# Mainboard.net
KiCad netlist of a schematic drawn in EasyEDA
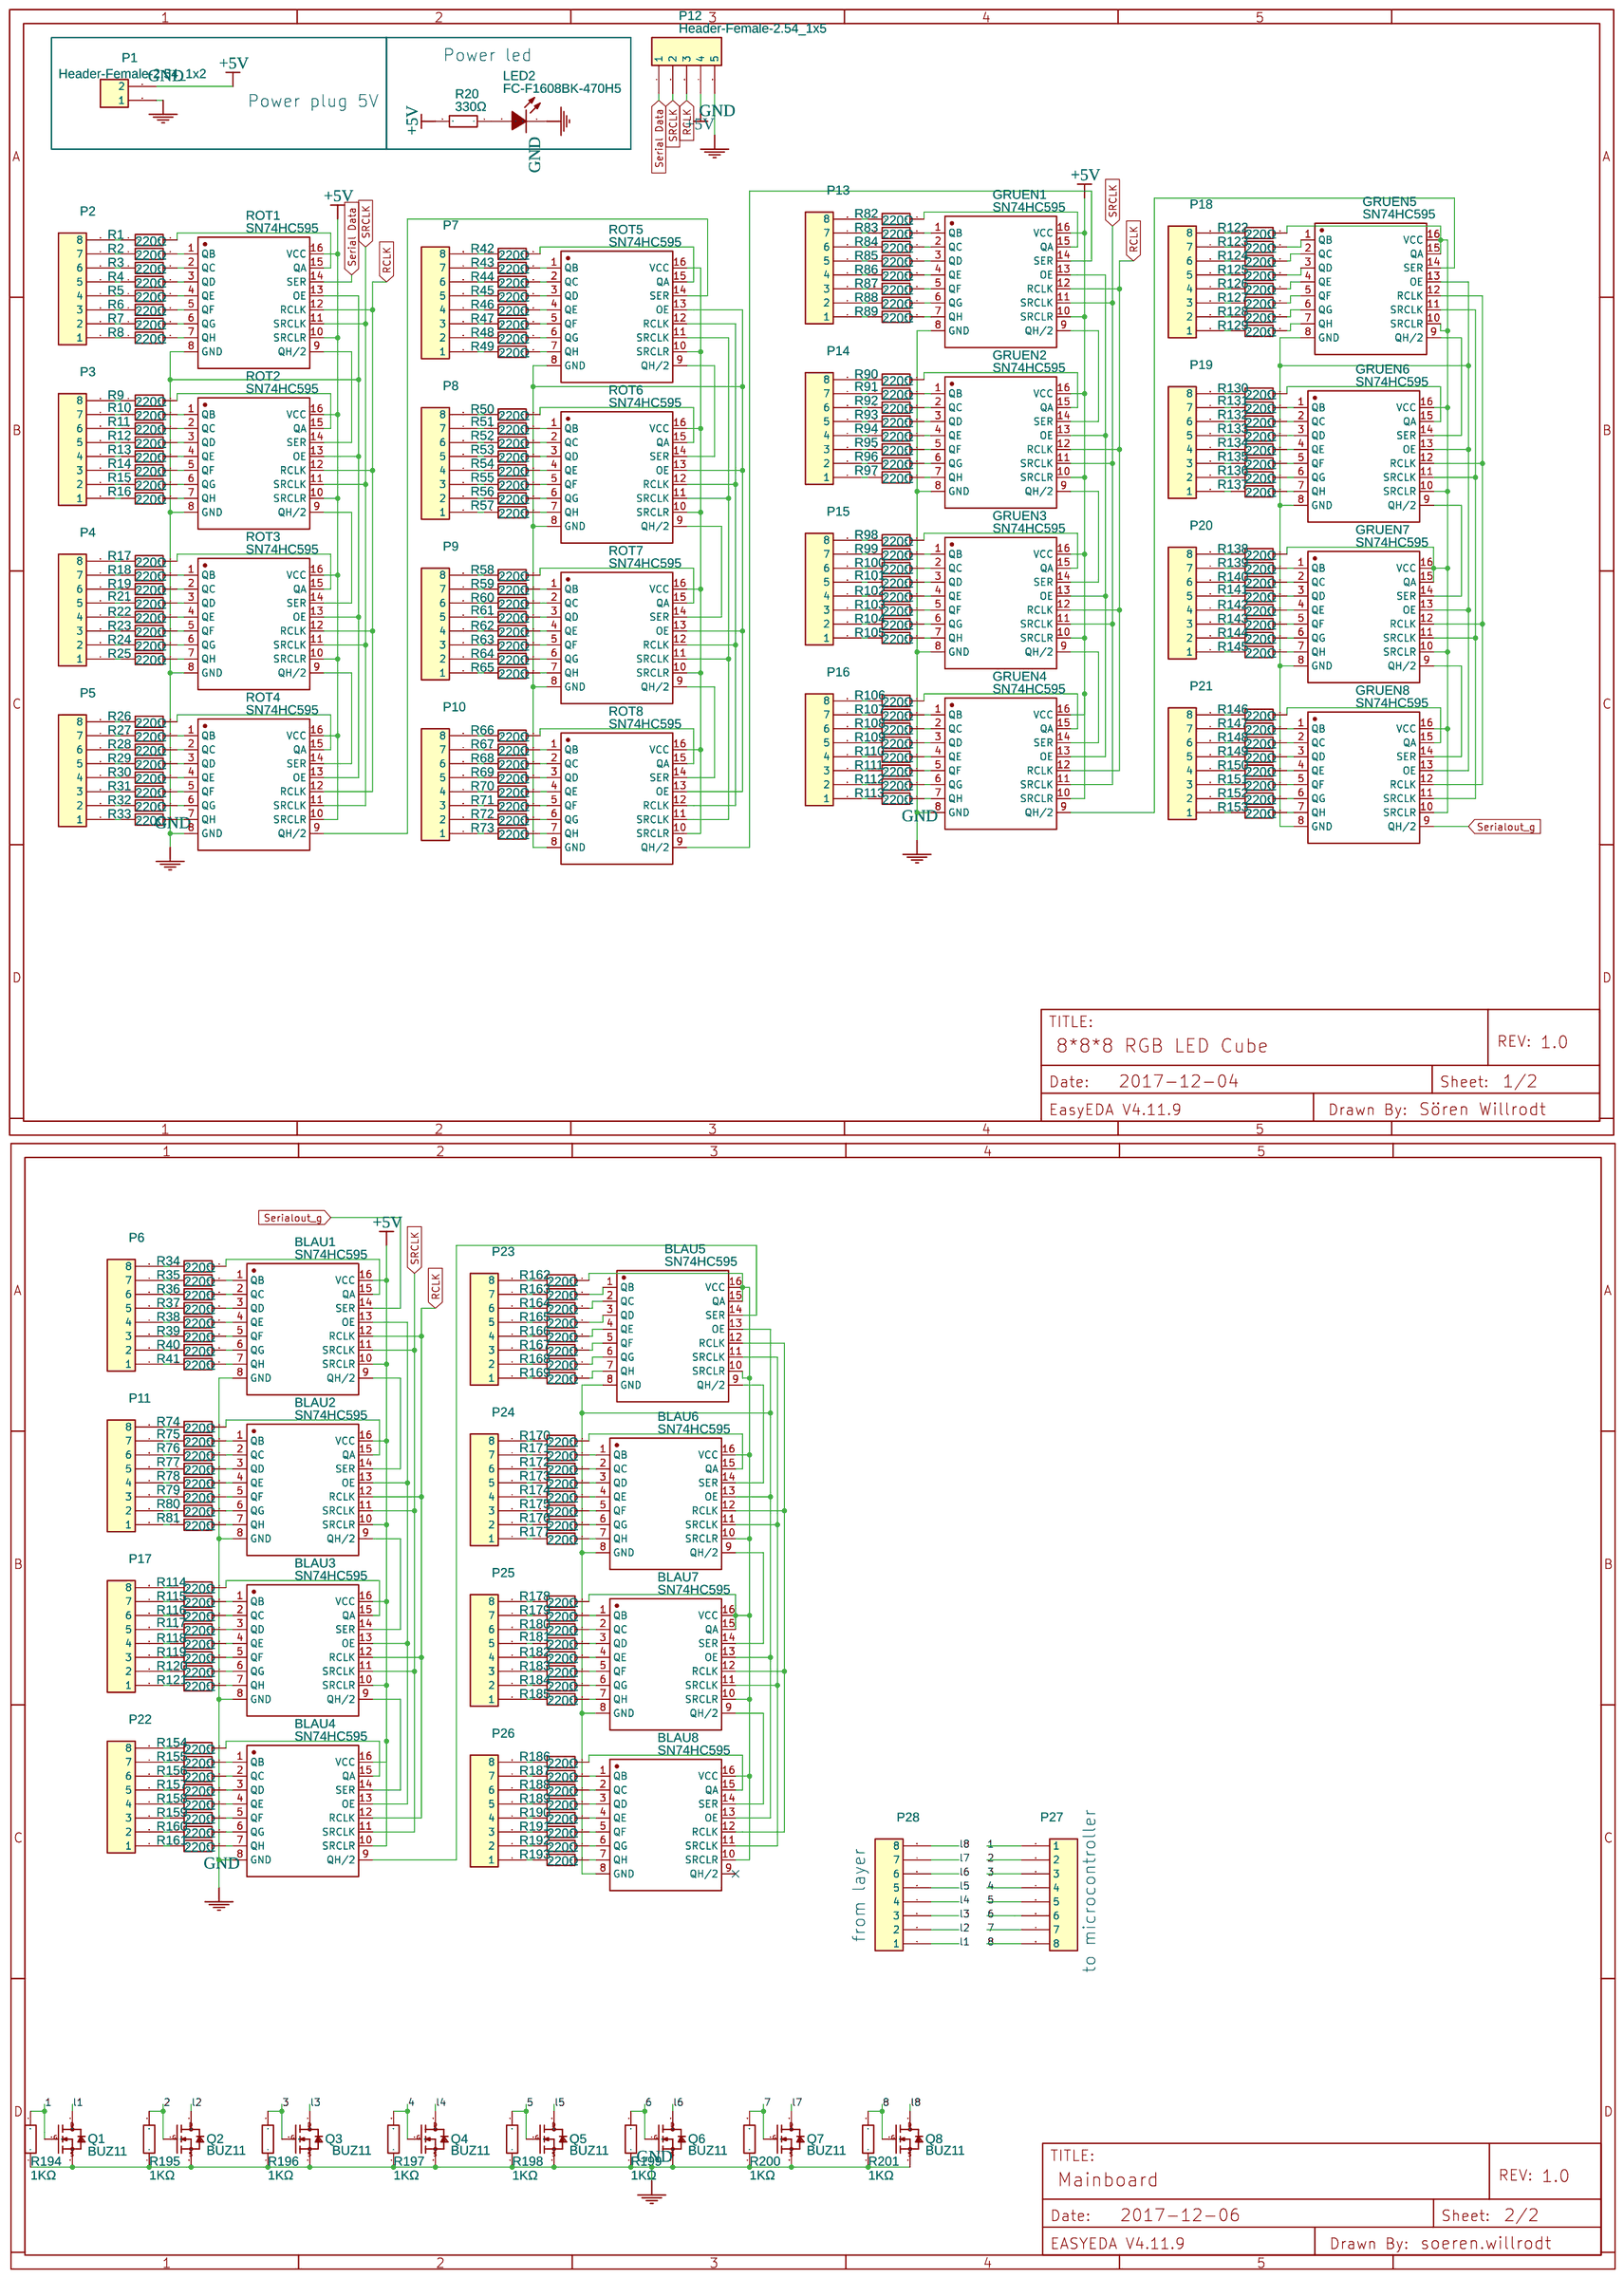
[diagram p0: schematic sheet]

(export (version "E")
  (design (tool "Eeschema 10.0.6"))
  (components
    (comp (ref "BLAU1")
      (value "SN74HC595")
      (fields (field (name "BOM_Manufacturer Part") "SN74HC595ANSR"))
      (libsource (lib "") (part "Unknown_210_900"))
    )
    (comp (ref "BLAU2")
      (value "SN74HC595")
      (fields (field (name "BOM_Manufacturer Part") "SN74HC595ANSR"))
      (libsource (lib "") (part "Unknown_210_1015"))
    )
    (comp (ref "BLAU3")
      (value "SN74HC595")
      (fields (field (name "BOM_Manufacturer Part") "SN74HC595ANSR"))
      (libsource (lib "") (part "Unknown_210_1130"))
    )
    (comp (ref "BLAU4")
      (value "SN74HC595")
      (fields (field (name "BOM_Manufacturer Part") "SN74HC595ANSR"))
      (libsource (lib "") (part "Unknown_210_1245"))
    )
    (comp (ref "BLAU5")
      (value "SN74HC595")
      (fields (field (name "BOM_Manufacturer Part") "SN74HC595ANSR"))
      (libsource (lib "") (part "Unknown_475_905"))
    )
    (comp (ref "BLAU6")
      (value "SN74HC595")
      (fields (field (name "BOM_Manufacturer Part") "SN74HC595ANSR"))
      (libsource (lib "") (part "Unknown_470_1025"))
    )
    (comp (ref "BLAU7")
      (value "SN74HC595")
      (fields (field (name "BOM_Manufacturer Part") "SN74HC595ANSR"))
      (libsource (lib "") (part "Unknown_470_1140"))
    )
    (comp (ref "BLAU8")
      (value "SN74HC595")
      (fields (field (name "BOM_Manufacturer Part") "SN74HC595ANSR"))
      (libsource (lib "") (part "Unknown_470_1255"))
    )
    (comp (ref "GRUEN1")
      (value "SN74HC595")
      (fields (field (name "BOM_Manufacturer Part") "SN74HC595ANSR"))
      (libsource (lib "") (part "Unknown_710_150"))
    )
    (comp (ref "GRUEN2")
      (value "SN74HC595")
      (fields (field (name "BOM_Manufacturer Part") "SN74HC595ANSR"))
      (libsource (lib "") (part "Unknown_710_265"))
    )
    (comp (ref "GRUEN3")
      (value "SN74HC595")
      (fields (field (name "BOM_Manufacturer Part") "SN74HC595ANSR"))
      (libsource (lib "") (part "Unknown_710_380"))
    )
    (comp (ref "GRUEN4")
      (value "SN74HC595")
      (fields (field (name "BOM_Manufacturer Part") "SN74HC595ANSR"))
      (libsource (lib "") (part "Unknown_710_495"))
    )
    (comp (ref "GRUEN5")
      (value "SN74HC595")
      (fields (field (name "BOM_Manufacturer Part") "SN74HC595ANSR"))
      (libsource (lib "") (part "Unknown_975_155"))
    )
    (comp (ref "GRUEN6")
      (value "SN74HC595")
      (fields (field (name "BOM_Manufacturer Part") "SN74HC595ANSR"))
      (libsource (lib "") (part "Unknown_970_275"))
    )
    (comp (ref "GRUEN7")
      (value "SN74HC595")
      (fields (field (name "BOM_Manufacturer Part") "SN74HC595ANSR"))
      (libsource (lib "") (part "Unknown_970_390"))
    )
    (comp (ref "GRUEN8")
      (value "SN74HC595")
      (fields (field (name "BOM_Manufacturer Part") "SN74HC595ANSR"))
      (libsource (lib "") (part "Unknown_970_505"))
    )
    (comp (ref "LED2") (value "FC-F1608BK-470H5") (libsource (lib "") (part "Unknown_365_80")))
    (comp (ref "P1") (value "Header-Female-2.54_1x2") (libsource (lib "") (part "Unknown_90_60")))
    (comp (ref "P2") (value "Header-Female-2.54_1x8") (libsource (lib "") (part "Unknown_60_200")))
    (comp (ref "P3") (value "Header-Female-2.54_1x8") (libsource (lib "") (part "Unknown_60_315")))
    (comp (ref "P4") (value "Header-Female-2.54_1x8") (libsource (lib "") (part "Unknown_60_430")))
    (comp (ref "P5") (value "Header-Female-2.54_1x8") (libsource (lib "") (part "Unknown_60_545")))
    (comp (ref "P6") (value "Header-Female-2.54_1x8") (libsource (lib "") (part "Unknown_95_935")))
    (comp (ref "P7") (value "Header-Female-2.54_1x8") (libsource (lib "") (part "Unknown_320_210")))
    (comp (ref "P8") (value "Header-Female-2.54_1x8") (libsource (lib "") (part "Unknown_320_325")))
    (comp (ref "P9") (value "Header-Female-2.54_1x8") (libsource (lib "") (part "Unknown_320_440")))
    (comp (ref "P10") (value "Header-Female-2.54_1x8") (libsource (lib "") (part "Unknown_320_555")))
    (comp (ref "P11") (value "Header-Female-2.54_1x8") (libsource (lib "") (part "Unknown_95_1050")))
    (comp (ref "P12") (value "Header-Female-2.54_1x5") (libsource (lib "") (part "Unknown_485_45")))
    (comp (ref "P13") (value "Header-Female-2.54_1x8") (libsource (lib "") (part "Unknown_595_185")))
    (comp (ref "P14") (value "Header-Female-2.54_1x8") (libsource (lib "") (part "Unknown_595_300")))
    (comp (ref "P15") (value "Header-Female-2.54_1x8") (libsource (lib "") (part "Unknown_595_415")))
    (comp (ref "P16") (value "Header-Female-2.54_1x8") (libsource (lib "") (part "Unknown_595_530")))
    (comp (ref "P17") (value "Header-Female-2.54_1x8") (libsource (lib "") (part "Unknown_95_1165")))
    (comp (ref "P18") (value "Header-Female-2.54_1x8") (libsource (lib "") (part "Unknown_855_195")))
    (comp (ref "P19") (value "Header-Female-2.54_1x8") (libsource (lib "") (part "Unknown_855_310")))
    (comp (ref "P20") (value "Header-Female-2.54_1x8") (libsource (lib "") (part "Unknown_855_425")))
    (comp (ref "P21") (value "Header-Female-2.54_1x8") (libsource (lib "") (part "Unknown_855_540")))
    (comp (ref "P22") (value "Header-Female-2.54_1x8") (libsource (lib "") (part "Unknown_95_1280")))
    (comp (ref "P23") (value "Header-Female-2.54_1x8") (libsource (lib "") (part "Unknown_355_945")))
    (comp (ref "P24") (value "Header-Female-2.54_1x8") (libsource (lib "") (part "Unknown_355_1060")))
    (comp (ref "P25") (value "Header-Female-2.54_1x8") (libsource (lib "") (part "Unknown_355_1175")))
    (comp (ref "P26") (value "Header-Female-2.54_1x8") (libsource (lib "") (part "Unknown_355_1290")))
    (comp (ref "P27") (value "Header-Female-2.54_1x8") (libsource (lib "") (part "Unknown_740_1350")))
    (comp (ref "P28") (value "Header-Female-2.54_1x8") (libsource (lib "") (part "Unknown_645_1350")))
    (comp (ref "Q1")
      (value "BUZ11")
      (fields (field (name "BOM_Manufacturer Part") "?"))
      (libsource (lib "") (part "Unknown_45_1525"))
    )
    (comp (ref "Q2")
      (value "BUZ11")
      (fields (field (name "BOM_Manufacturer Part") "?"))
      (libsource (lib "") (part "Unknown_130_1525"))
    )
    (comp (ref "Q3")
      (value "BUZ11")
      (fields (field (name "BOM_Manufacturer Part") "?"))
      (libsource (lib "") (part "Unknown_215_1525"))
    )
    (comp (ref "Q4")
      (value "BUZ11")
      (fields (field (name "BOM_Manufacturer Part") "?"))
      (libsource (lib "") (part "Unknown_305_1525"))
    )
    (comp (ref "Q5")
      (value "BUZ11")
      (fields (field (name "BOM_Manufacturer Part") "?"))
      (libsource (lib "") (part "Unknown_390_1525"))
    )
    (comp (ref "Q6")
      (value "BUZ11")
      (fields (field (name "BOM_Manufacturer Part") "?"))
      (libsource (lib "") (part "Unknown_475_1525"))
    )
    (comp (ref "Q7")
      (value "BUZ11")
      (fields (field (name "BOM_Manufacturer Part") "?"))
      (libsource (lib "") (part "Unknown_560_1525"))
    )
    (comp (ref "Q8")
      (value "BUZ11")
      (fields (field (name "BOM_Manufacturer Part") "?"))
      (libsource (lib "") (part "Unknown_645_1525"))
    )
    (comp (ref "R1")
      (value "220Ω")
      (fields (field (name "BOM_Manufacturer Part") "25121WJ0221T4E"))
      (libsource (lib "") (part "Unknown_100_165"))
    )
    (comp (ref "R2")
      (value "220Ω")
      (fields (field (name "BOM_Manufacturer Part") "25121WJ0221T4E"))
      (libsource (lib "") (part "Unknown_100_175"))
    )
    (comp (ref "R3")
      (value "220Ω")
      (fields (field (name "BOM_Manufacturer Part") "25121WJ0221T4E"))
      (libsource (lib "") (part "Unknown_100_185"))
    )
    (comp (ref "R4")
      (value "220Ω")
      (fields (field (name "BOM_Manufacturer Part") "25121WJ0221T4E"))
      (libsource (lib "") (part "Unknown_100_195"))
    )
    (comp (ref "R5")
      (value "220Ω")
      (fields (field (name "BOM_Manufacturer Part") "25121WJ0221T4E"))
      (libsource (lib "") (part "Unknown_100_205"))
    )
    (comp (ref "R6")
      (value "220Ω")
      (fields (field (name "BOM_Manufacturer Part") "25121WJ0221T4E"))
      (libsource (lib "") (part "Unknown_100_215"))
    )
    (comp (ref "R7")
      (value "220Ω")
      (fields (field (name "BOM_Manufacturer Part") "25121WJ0221T4E"))
      (libsource (lib "") (part "Unknown_100_225"))
    )
    (comp (ref "R8")
      (value "220Ω")
      (fields (field (name "BOM_Manufacturer Part") "25121WJ0221T4E"))
      (libsource (lib "") (part "Unknown_100_235"))
    )
    (comp (ref "R9")
      (value "220Ω")
      (fields (field (name "BOM_Manufacturer Part") "25121WJ0221T4E"))
      (libsource (lib "") (part "Unknown_100_280"))
    )
    (comp (ref "R10")
      (value "220Ω")
      (fields (field (name "BOM_Manufacturer Part") "25121WJ0221T4E"))
      (libsource (lib "") (part "Unknown_100_290"))
    )
    (comp (ref "R11")
      (value "220Ω")
      (fields (field (name "BOM_Manufacturer Part") "25121WJ0221T4E"))
      (libsource (lib "") (part "Unknown_100_300"))
    )
    (comp (ref "R12")
      (value "220Ω")
      (fields (field (name "BOM_Manufacturer Part") "25121WJ0221T4E"))
      (libsource (lib "") (part "Unknown_100_310"))
    )
    (comp (ref "R13")
      (value "220Ω")
      (fields (field (name "BOM_Manufacturer Part") "25121WJ0221T4E"))
      (libsource (lib "") (part "Unknown_100_320"))
    )
    (comp (ref "R14")
      (value "220Ω")
      (fields (field (name "BOM_Manufacturer Part") "25121WJ0221T4E"))
      (libsource (lib "") (part "Unknown_100_330"))
    )
    (comp (ref "R15")
      (value "220Ω")
      (fields (field (name "BOM_Manufacturer Part") "25121WJ0221T4E"))
      (libsource (lib "") (part "Unknown_100_340"))
    )
    (comp (ref "R16")
      (value "220Ω")
      (fields (field (name "BOM_Manufacturer Part") "25121WJ0221T4E"))
      (libsource (lib "") (part "Unknown_100_350"))
    )
    (comp (ref "R17")
      (value "220Ω")
      (fields (field (name "BOM_Manufacturer Part") "25121WJ0221T4E"))
      (libsource (lib "") (part "Unknown_100_395"))
    )
    (comp (ref "R18")
      (value "220Ω")
      (fields (field (name "BOM_Manufacturer Part") "25121WJ0221T4E"))
      (libsource (lib "") (part "Unknown_100_405"))
    )
    (comp (ref "R19")
      (value "220Ω")
      (fields (field (name "BOM_Manufacturer Part") "25121WJ0221T4E"))
      (libsource (lib "") (part "Unknown_100_415"))
    )
    (comp (ref "R20")
      (value "330Ω")
      (fields (field (name "BOM_Manufacturer Part") "0603WAF3300T5E"))
      (libsource (lib "") (part "Unknown_325_80"))
    )
    (comp (ref "R21")
      (value "220Ω")
      (fields (field (name "BOM_Manufacturer Part") "25121WJ0221T4E"))
      (libsource (lib "") (part "Unknown_100_425"))
    )
    (comp (ref "R22")
      (value "220Ω")
      (fields (field (name "BOM_Manufacturer Part") "25121WJ0221T4E"))
      (libsource (lib "") (part "Unknown_100_435"))
    )
    (comp (ref "R23")
      (value "220Ω")
      (fields (field (name "BOM_Manufacturer Part") "25121WJ0221T4E"))
      (libsource (lib "") (part "Unknown_100_445"))
    )
    (comp (ref "R24")
      (value "220Ω")
      (fields (field (name "BOM_Manufacturer Part") "25121WJ0221T4E"))
      (libsource (lib "") (part "Unknown_100_455"))
    )
    (comp (ref "R25")
      (value "220Ω")
      (fields (field (name "BOM_Manufacturer Part") "25121WJ0221T4E"))
      (libsource (lib "") (part "Unknown_100_465"))
    )
    (comp (ref "R26")
      (value "220Ω")
      (fields (field (name "BOM_Manufacturer Part") "25121WJ0221T4E"))
      (libsource (lib "") (part "Unknown_100_510"))
    )
    (comp (ref "R27")
      (value "220Ω")
      (fields (field (name "BOM_Manufacturer Part") "25121WJ0221T4E"))
      (libsource (lib "") (part "Unknown_100_520"))
    )
    (comp (ref "R28")
      (value "220Ω")
      (fields (field (name "BOM_Manufacturer Part") "25121WJ0221T4E"))
      (libsource (lib "") (part "Unknown_100_530"))
    )
    (comp (ref "R29")
      (value "220Ω")
      (fields (field (name "BOM_Manufacturer Part") "25121WJ0221T4E"))
      (libsource (lib "") (part "Unknown_100_540"))
    )
    (comp (ref "R30")
      (value "220Ω")
      (fields (field (name "BOM_Manufacturer Part") "25121WJ0221T4E"))
      (libsource (lib "") (part "Unknown_100_550"))
    )
    (comp (ref "R31")
      (value "220Ω")
      (fields (field (name "BOM_Manufacturer Part") "25121WJ0221T4E"))
      (libsource (lib "") (part "Unknown_100_560"))
    )
    (comp (ref "R32")
      (value "220Ω")
      (fields (field (name "BOM_Manufacturer Part") "25121WJ0221T4E"))
      (libsource (lib "") (part "Unknown_100_570"))
    )
    (comp (ref "R33")
      (value "220Ω")
      (fields (field (name "BOM_Manufacturer Part") "25121WJ0221T4E"))
      (libsource (lib "") (part "Unknown_100_580"))
    )
    (comp (ref "R34")
      (value "220Ω")
      (fields (field (name "BOM_Manufacturer Part") "25121WJ0221T4E"))
      (libsource (lib "") (part "Unknown_135_900"))
    )
    (comp (ref "R35")
      (value "220Ω")
      (fields (field (name "BOM_Manufacturer Part") "25121WJ0221T4E"))
      (libsource (lib "") (part "Unknown_135_910"))
    )
    (comp (ref "R36")
      (value "220Ω")
      (fields (field (name "BOM_Manufacturer Part") "25121WJ0221T4E"))
      (libsource (lib "") (part "Unknown_135_920"))
    )
    (comp (ref "R37")
      (value "220Ω")
      (fields (field (name "BOM_Manufacturer Part") "25121WJ0221T4E"))
      (libsource (lib "") (part "Unknown_135_930"))
    )
    (comp (ref "R38")
      (value "220Ω")
      (fields (field (name "BOM_Manufacturer Part") "25121WJ0221T4E"))
      (libsource (lib "") (part "Unknown_135_940"))
    )
    (comp (ref "R39")
      (value "220Ω")
      (fields (field (name "BOM_Manufacturer Part") "25121WJ0221T4E"))
      (libsource (lib "") (part "Unknown_135_950"))
    )
    (comp (ref "R40")
      (value "220Ω")
      (fields (field (name "BOM_Manufacturer Part") "25121WJ0221T4E"))
      (libsource (lib "") (part "Unknown_135_960"))
    )
    (comp (ref "R41")
      (value "220Ω")
      (fields (field (name "BOM_Manufacturer Part") "25121WJ0221T4E"))
      (libsource (lib "") (part "Unknown_135_970"))
    )
    (comp (ref "R42")
      (value "220Ω")
      (fields (field (name "BOM_Manufacturer Part") "25121WJ0221T4E"))
      (libsource (lib "") (part "Unknown_360_175"))
    )
    (comp (ref "R43")
      (value "220Ω")
      (fields (field (name "BOM_Manufacturer Part") "25121WJ0221T4E"))
      (libsource (lib "") (part "Unknown_360_185"))
    )
    (comp (ref "R44")
      (value "220Ω")
      (fields (field (name "BOM_Manufacturer Part") "25121WJ0221T4E"))
      (libsource (lib "") (part "Unknown_360_195"))
    )
    (comp (ref "R45")
      (value "220Ω")
      (fields (field (name "BOM_Manufacturer Part") "25121WJ0221T4E"))
      (libsource (lib "") (part "Unknown_360_205"))
    )
    (comp (ref "R46")
      (value "220Ω")
      (fields (field (name "BOM_Manufacturer Part") "25121WJ0221T4E"))
      (libsource (lib "") (part "Unknown_360_215"))
    )
    (comp (ref "R47")
      (value "220Ω")
      (fields (field (name "BOM_Manufacturer Part") "25121WJ0221T4E"))
      (libsource (lib "") (part "Unknown_360_225"))
    )
    (comp (ref "R48")
      (value "220Ω")
      (fields (field (name "BOM_Manufacturer Part") "25121WJ0221T4E"))
      (libsource (lib "") (part "Unknown_360_235"))
    )
    (comp (ref "R49")
      (value "220Ω")
      (fields (field (name "BOM_Manufacturer Part") "25121WJ0221T4E"))
      (libsource (lib "") (part "Unknown_360_245"))
    )
    (comp (ref "R50")
      (value "220Ω")
      (fields (field (name "BOM_Manufacturer Part") "25121WJ0221T4E"))
      (libsource (lib "") (part "Unknown_360_290"))
    )
    (comp (ref "R51")
      (value "220Ω")
      (fields (field (name "BOM_Manufacturer Part") "25121WJ0221T4E"))
      (libsource (lib "") (part "Unknown_360_300"))
    )
    (comp (ref "R52")
      (value "220Ω")
      (fields (field (name "BOM_Manufacturer Part") "25121WJ0221T4E"))
      (libsource (lib "") (part "Unknown_360_310"))
    )
    (comp (ref "R53")
      (value "220Ω")
      (fields (field (name "BOM_Manufacturer Part") "25121WJ0221T4E"))
      (libsource (lib "") (part "Unknown_360_320"))
    )
    (comp (ref "R54")
      (value "220Ω")
      (fields (field (name "BOM_Manufacturer Part") "25121WJ0221T4E"))
      (libsource (lib "") (part "Unknown_360_330"))
    )
    (comp (ref "R55")
      (value "220Ω")
      (fields (field (name "BOM_Manufacturer Part") "25121WJ0221T4E"))
      (libsource (lib "") (part "Unknown_360_340"))
    )
    (comp (ref "R56")
      (value "220Ω")
      (fields (field (name "BOM_Manufacturer Part") "25121WJ0221T4E"))
      (libsource (lib "") (part "Unknown_360_350"))
    )
    (comp (ref "R57")
      (value "220Ω")
      (fields (field (name "BOM_Manufacturer Part") "25121WJ0221T4E"))
      (libsource (lib "") (part "Unknown_360_360"))
    )
    (comp (ref "R58")
      (value "220Ω")
      (fields (field (name "BOM_Manufacturer Part") "25121WJ0221T4E"))
      (libsource (lib "") (part "Unknown_360_405"))
    )
    (comp (ref "R59")
      (value "220Ω")
      (fields (field (name "BOM_Manufacturer Part") "25121WJ0221T4E"))
      (libsource (lib "") (part "Unknown_360_415"))
    )
    (comp (ref "R60")
      (value "220Ω")
      (fields (field (name "BOM_Manufacturer Part") "25121WJ0221T4E"))
      (libsource (lib "") (part "Unknown_360_425"))
    )
    (comp (ref "R61")
      (value "220Ω")
      (fields (field (name "BOM_Manufacturer Part") "25121WJ0221T4E"))
      (libsource (lib "") (part "Unknown_360_435"))
    )
    (comp (ref "R62")
      (value "220Ω")
      (fields (field (name "BOM_Manufacturer Part") "25121WJ0221T4E"))
      (libsource (lib "") (part "Unknown_360_445"))
    )
    (comp (ref "R63")
      (value "220Ω")
      (fields (field (name "BOM_Manufacturer Part") "25121WJ0221T4E"))
      (libsource (lib "") (part "Unknown_360_455"))
    )
    (comp (ref "R64")
      (value "220Ω")
      (fields (field (name "BOM_Manufacturer Part") "25121WJ0221T4E"))
      (libsource (lib "") (part "Unknown_360_465"))
    )
    (comp (ref "R65")
      (value "220Ω")
      (fields (field (name "BOM_Manufacturer Part") "25121WJ0221T4E"))
      (libsource (lib "") (part "Unknown_360_475"))
    )
    (comp (ref "R66")
      (value "220Ω")
      (fields (field (name "BOM_Manufacturer Part") "25121WJ0221T4E"))
      (libsource (lib "") (part "Unknown_360_520"))
    )
    (comp (ref "R67")
      (value "220Ω")
      (fields (field (name "BOM_Manufacturer Part") "25121WJ0221T4E"))
      (libsource (lib "") (part "Unknown_360_530"))
    )
    (comp (ref "R68")
      (value "220Ω")
      (fields (field (name "BOM_Manufacturer Part") "25121WJ0221T4E"))
      (libsource (lib "") (part "Unknown_360_540"))
    )
    (comp (ref "R69")
      (value "220Ω")
      (fields (field (name "BOM_Manufacturer Part") "25121WJ0221T4E"))
      (libsource (lib "") (part "Unknown_360_550"))
    )
    (comp (ref "R70")
      (value "220Ω")
      (fields (field (name "BOM_Manufacturer Part") "25121WJ0221T4E"))
      (libsource (lib "") (part "Unknown_360_560"))
    )
    (comp (ref "R71")
      (value "220Ω")
      (fields (field (name "BOM_Manufacturer Part") "25121WJ0221T4E"))
      (libsource (lib "") (part "Unknown_360_570"))
    )
    (comp (ref "R72")
      (value "220Ω")
      (fields (field (name "BOM_Manufacturer Part") "25121WJ0221T4E"))
      (libsource (lib "") (part "Unknown_360_580"))
    )
    (comp (ref "R73")
      (value "220Ω")
      (fields (field (name "BOM_Manufacturer Part") "25121WJ0221T4E"))
      (libsource (lib "") (part "Unknown_360_590"))
    )
    (comp (ref "R74")
      (value "220Ω")
      (fields (field (name "BOM_Manufacturer Part") "25121WJ0221T4E"))
      (libsource (lib "") (part "Unknown_135_1015"))
    )
    (comp (ref "R75")
      (value "220Ω")
      (fields (field (name "BOM_Manufacturer Part") "25121WJ0221T4E"))
      (libsource (lib "") (part "Unknown_135_1025"))
    )
    (comp (ref "R76")
      (value "220Ω")
      (fields (field (name "BOM_Manufacturer Part") "25121WJ0221T4E"))
      (libsource (lib "") (part "Unknown_135_1035"))
    )
    (comp (ref "R77")
      (value "220Ω")
      (fields (field (name "BOM_Manufacturer Part") "25121WJ0221T4E"))
      (libsource (lib "") (part "Unknown_135_1045"))
    )
    (comp (ref "R78")
      (value "220Ω")
      (fields (field (name "BOM_Manufacturer Part") "25121WJ0221T4E"))
      (libsource (lib "") (part "Unknown_135_1055"))
    )
    (comp (ref "R79")
      (value "220Ω")
      (fields (field (name "BOM_Manufacturer Part") "25121WJ0221T4E"))
      (libsource (lib "") (part "Unknown_135_1065"))
    )
    (comp (ref "R80")
      (value "220Ω")
      (fields (field (name "BOM_Manufacturer Part") "25121WJ0221T4E"))
      (libsource (lib "") (part "Unknown_135_1075"))
    )
    (comp (ref "R81")
      (value "220Ω")
      (fields (field (name "BOM_Manufacturer Part") "25121WJ0221T4E"))
      (libsource (lib "") (part "Unknown_135_1085"))
    )
    (comp (ref "R82")
      (value "220Ω")
      (fields (field (name "BOM_Manufacturer Part") "25121WJ0221T4E"))
      (libsource (lib "") (part "Unknown_635_150"))
    )
    (comp (ref "R83")
      (value "220Ω")
      (fields (field (name "BOM_Manufacturer Part") "25121WJ0221T4E"))
      (libsource (lib "") (part "Unknown_635_160"))
    )
    (comp (ref "R84")
      (value "220Ω")
      (fields (field (name "BOM_Manufacturer Part") "25121WJ0221T4E"))
      (libsource (lib "") (part "Unknown_635_170"))
    )
    (comp (ref "R85")
      (value "220Ω")
      (fields (field (name "BOM_Manufacturer Part") "25121WJ0221T4E"))
      (libsource (lib "") (part "Unknown_635_180"))
    )
    (comp (ref "R86")
      (value "220Ω")
      (fields (field (name "BOM_Manufacturer Part") "25121WJ0221T4E"))
      (libsource (lib "") (part "Unknown_635_190"))
    )
    (comp (ref "R87")
      (value "220Ω")
      (fields (field (name "BOM_Manufacturer Part") "25121WJ0221T4E"))
      (libsource (lib "") (part "Unknown_635_200"))
    )
    (comp (ref "R88")
      (value "220Ω")
      (fields (field (name "BOM_Manufacturer Part") "25121WJ0221T4E"))
      (libsource (lib "") (part "Unknown_635_210"))
    )
    (comp (ref "R89")
      (value "220Ω")
      (fields (field (name "BOM_Manufacturer Part") "25121WJ0221T4E"))
      (libsource (lib "") (part "Unknown_635_220"))
    )
    (comp (ref "R90")
      (value "220Ω")
      (fields (field (name "BOM_Manufacturer Part") "25121WJ0221T4E"))
      (libsource (lib "") (part "Unknown_635_265"))
    )
    (comp (ref "R91")
      (value "220Ω")
      (fields (field (name "BOM_Manufacturer Part") "25121WJ0221T4E"))
      (libsource (lib "") (part "Unknown_635_275"))
    )
    (comp (ref "R92")
      (value "220Ω")
      (fields (field (name "BOM_Manufacturer Part") "25121WJ0221T4E"))
      (libsource (lib "") (part "Unknown_635_285"))
    )
    (comp (ref "R93")
      (value "220Ω")
      (fields (field (name "BOM_Manufacturer Part") "25121WJ0221T4E"))
      (libsource (lib "") (part "Unknown_635_295"))
    )
    (comp (ref "R94")
      (value "220Ω")
      (fields (field (name "BOM_Manufacturer Part") "25121WJ0221T4E"))
      (libsource (lib "") (part "Unknown_635_305"))
    )
    (comp (ref "R95")
      (value "220Ω")
      (fields (field (name "BOM_Manufacturer Part") "25121WJ0221T4E"))
      (libsource (lib "") (part "Unknown_635_315"))
    )
    (comp (ref "R96")
      (value "220Ω")
      (fields (field (name "BOM_Manufacturer Part") "25121WJ0221T4E"))
      (libsource (lib "") (part "Unknown_635_325"))
    )
    (comp (ref "R97")
      (value "220Ω")
      (fields (field (name "BOM_Manufacturer Part") "25121WJ0221T4E"))
      (libsource (lib "") (part "Unknown_635_335"))
    )
    (comp (ref "R98")
      (value "220Ω")
      (fields (field (name "BOM_Manufacturer Part") "25121WJ0221T4E"))
      (libsource (lib "") (part "Unknown_635_380"))
    )
    (comp (ref "R99")
      (value "220Ω")
      (fields (field (name "BOM_Manufacturer Part") "25121WJ0221T4E"))
      (libsource (lib "") (part "Unknown_635_390"))
    )
    (comp (ref "R100")
      (value "220Ω")
      (fields (field (name "BOM_Manufacturer Part") "25121WJ0221T4E"))
      (libsource (lib "") (part "Unknown_635_400"))
    )
    (comp (ref "R101")
      (value "220Ω")
      (fields (field (name "BOM_Manufacturer Part") "25121WJ0221T4E"))
      (libsource (lib "") (part "Unknown_635_410"))
    )
    (comp (ref "R102")
      (value "220Ω")
      (fields (field (name "BOM_Manufacturer Part") "25121WJ0221T4E"))
      (libsource (lib "") (part "Unknown_635_420"))
    )
    (comp (ref "R103")
      (value "220Ω")
      (fields (field (name "BOM_Manufacturer Part") "25121WJ0221T4E"))
      (libsource (lib "") (part "Unknown_635_430"))
    )
    (comp (ref "R104")
      (value "220Ω")
      (fields (field (name "BOM_Manufacturer Part") "25121WJ0221T4E"))
      (libsource (lib "") (part "Unknown_635_440"))
    )
    (comp (ref "R105")
      (value "220Ω")
      (fields (field (name "BOM_Manufacturer Part") "25121WJ0221T4E"))
      (libsource (lib "") (part "Unknown_635_450"))
    )
    (comp (ref "R106")
      (value "220Ω")
      (fields (field (name "BOM_Manufacturer Part") "25121WJ0221T4E"))
      (libsource (lib "") (part "Unknown_635_495"))
    )
    (comp (ref "R107")
      (value "220Ω")
      (fields (field (name "BOM_Manufacturer Part") "25121WJ0221T4E"))
      (libsource (lib "") (part "Unknown_635_505"))
    )
    (comp (ref "R108")
      (value "220Ω")
      (fields (field (name "BOM_Manufacturer Part") "25121WJ0221T4E"))
      (libsource (lib "") (part "Unknown_635_515"))
    )
    (comp (ref "R109")
      (value "220Ω")
      (fields (field (name "BOM_Manufacturer Part") "25121WJ0221T4E"))
      (libsource (lib "") (part "Unknown_635_525"))
    )
    (comp (ref "R110")
      (value "220Ω")
      (fields (field (name "BOM_Manufacturer Part") "25121WJ0221T4E"))
      (libsource (lib "") (part "Unknown_635_535"))
    )
    (comp (ref "R111")
      (value "220Ω")
      (fields (field (name "BOM_Manufacturer Part") "25121WJ0221T4E"))
      (libsource (lib "") (part "Unknown_635_545"))
    )
    (comp (ref "R112")
      (value "220Ω")
      (fields (field (name "BOM_Manufacturer Part") "25121WJ0221T4E"))
      (libsource (lib "") (part "Unknown_635_555"))
    )
    (comp (ref "R113")
      (value "220Ω")
      (fields (field (name "BOM_Manufacturer Part") "25121WJ0221T4E"))
      (libsource (lib "") (part "Unknown_635_565"))
    )
    (comp (ref "R114")
      (value "220Ω")
      (fields (field (name "BOM_Manufacturer Part") "25121WJ0221T4E"))
      (libsource (lib "") (part "Unknown_135_1130"))
    )
    (comp (ref "R115")
      (value "220Ω")
      (fields (field (name "BOM_Manufacturer Part") "25121WJ0221T4E"))
      (libsource (lib "") (part "Unknown_135_1140"))
    )
    (comp (ref "R116")
      (value "220Ω")
      (fields (field (name "BOM_Manufacturer Part") "25121WJ0221T4E"))
      (libsource (lib "") (part "Unknown_135_1150"))
    )
    (comp (ref "R117")
      (value "220Ω")
      (fields (field (name "BOM_Manufacturer Part") "25121WJ0221T4E"))
      (libsource (lib "") (part "Unknown_135_1160"))
    )
    (comp (ref "R118")
      (value "220Ω")
      (fields (field (name "BOM_Manufacturer Part") "25121WJ0221T4E"))
      (libsource (lib "") (part "Unknown_135_1170"))
    )
    (comp (ref "R119")
      (value "220Ω")
      (fields (field (name "BOM_Manufacturer Part") "25121WJ0221T4E"))
      (libsource (lib "") (part "Unknown_135_1180"))
    )
    (comp (ref "R120")
      (value "220Ω")
      (fields (field (name "BOM_Manufacturer Part") "25121WJ0221T4E"))
      (libsource (lib "") (part "Unknown_135_1190"))
    )
    (comp (ref "R121")
      (value "220Ω")
      (fields (field (name "BOM_Manufacturer Part") "25121WJ0221T4E"))
      (libsource (lib "") (part "Unknown_135_1200"))
    )
    (comp (ref "R122")
      (value "220Ω")
      (fields (field (name "BOM_Manufacturer Part") "25121WJ0221T4E"))
      (libsource (lib "") (part "Unknown_895_160"))
    )
    (comp (ref "R123")
      (value "220Ω")
      (fields (field (name "BOM_Manufacturer Part") "25121WJ0221T4E"))
      (libsource (lib "") (part "Unknown_895_170"))
    )
    (comp (ref "R124")
      (value "220Ω")
      (fields (field (name "BOM_Manufacturer Part") "25121WJ0221T4E"))
      (libsource (lib "") (part "Unknown_895_180"))
    )
    (comp (ref "R125")
      (value "220Ω")
      (fields (field (name "BOM_Manufacturer Part") "25121WJ0221T4E"))
      (libsource (lib "") (part "Unknown_895_190"))
    )
    (comp (ref "R126")
      (value "220Ω")
      (fields (field (name "BOM_Manufacturer Part") "25121WJ0221T4E"))
      (libsource (lib "") (part "Unknown_895_200"))
    )
    (comp (ref "R127")
      (value "220Ω")
      (fields (field (name "BOM_Manufacturer Part") "25121WJ0221T4E"))
      (libsource (lib "") (part "Unknown_895_210"))
    )
    (comp (ref "R128")
      (value "220Ω")
      (fields (field (name "BOM_Manufacturer Part") "25121WJ0221T4E"))
      (libsource (lib "") (part "Unknown_895_220"))
    )
    (comp (ref "R129")
      (value "220Ω")
      (fields (field (name "BOM_Manufacturer Part") "25121WJ0221T4E"))
      (libsource (lib "") (part "Unknown_895_230"))
    )
    (comp (ref "R130")
      (value "220Ω")
      (fields (field (name "BOM_Manufacturer Part") "25121WJ0221T4E"))
      (libsource (lib "") (part "Unknown_895_275"))
    )
    (comp (ref "R131")
      (value "220Ω")
      (fields (field (name "BOM_Manufacturer Part") "25121WJ0221T4E"))
      (libsource (lib "") (part "Unknown_895_285"))
    )
    (comp (ref "R132")
      (value "220Ω")
      (fields (field (name "BOM_Manufacturer Part") "25121WJ0221T4E"))
      (libsource (lib "") (part "Unknown_895_295"))
    )
    (comp (ref "R133")
      (value "220Ω")
      (fields (field (name "BOM_Manufacturer Part") "25121WJ0221T4E"))
      (libsource (lib "") (part "Unknown_895_305"))
    )
    (comp (ref "R134")
      (value "220Ω")
      (fields (field (name "BOM_Manufacturer Part") "25121WJ0221T4E"))
      (libsource (lib "") (part "Unknown_895_315"))
    )
    (comp (ref "R135")
      (value "220Ω")
      (fields (field (name "BOM_Manufacturer Part") "25121WJ0221T4E"))
      (libsource (lib "") (part "Unknown_895_325"))
    )
    (comp (ref "R136")
      (value "220Ω")
      (fields (field (name "BOM_Manufacturer Part") "25121WJ0221T4E"))
      (libsource (lib "") (part "Unknown_895_335"))
    )
    (comp (ref "R137")
      (value "220Ω")
      (fields (field (name "BOM_Manufacturer Part") "25121WJ0221T4E"))
      (libsource (lib "") (part "Unknown_895_345"))
    )
    (comp (ref "R138")
      (value "220Ω")
      (fields (field (name "BOM_Manufacturer Part") "25121WJ0221T4E"))
      (libsource (lib "") (part "Unknown_895_390"))
    )
    (comp (ref "R139")
      (value "220Ω")
      (fields (field (name "BOM_Manufacturer Part") "25121WJ0221T4E"))
      (libsource (lib "") (part "Unknown_895_400"))
    )
    (comp (ref "R140")
      (value "220Ω")
      (fields (field (name "BOM_Manufacturer Part") "25121WJ0221T4E"))
      (libsource (lib "") (part "Unknown_895_410"))
    )
    (comp (ref "R141")
      (value "220Ω")
      (fields (field (name "BOM_Manufacturer Part") "25121WJ0221T4E"))
      (libsource (lib "") (part "Unknown_895_420"))
    )
    (comp (ref "R142")
      (value "220Ω")
      (fields (field (name "BOM_Manufacturer Part") "25121WJ0221T4E"))
      (libsource (lib "") (part "Unknown_895_430"))
    )
    (comp (ref "R143")
      (value "220Ω")
      (fields (field (name "BOM_Manufacturer Part") "25121WJ0221T4E"))
      (libsource (lib "") (part "Unknown_895_440"))
    )
    (comp (ref "R144")
      (value "220Ω")
      (fields (field (name "BOM_Manufacturer Part") "25121WJ0221T4E"))
      (libsource (lib "") (part "Unknown_895_450"))
    )
    (comp (ref "R145")
      (value "220Ω")
      (fields (field (name "BOM_Manufacturer Part") "25121WJ0221T4E"))
      (libsource (lib "") (part "Unknown_895_460"))
    )
    (comp (ref "R146")
      (value "220Ω")
      (fields (field (name "BOM_Manufacturer Part") "25121WJ0221T4E"))
      (libsource (lib "") (part "Unknown_895_505"))
    )
    (comp (ref "R147")
      (value "220Ω")
      (fields (field (name "BOM_Manufacturer Part") "25121WJ0221T4E"))
      (libsource (lib "") (part "Unknown_895_515"))
    )
    (comp (ref "R148")
      (value "220Ω")
      (fields (field (name "BOM_Manufacturer Part") "25121WJ0221T4E"))
      (libsource (lib "") (part "Unknown_895_525"))
    )
    (comp (ref "R149")
      (value "220Ω")
      (fields (field (name "BOM_Manufacturer Part") "25121WJ0221T4E"))
      (libsource (lib "") (part "Unknown_895_535"))
    )
    (comp (ref "R150")
      (value "220Ω")
      (fields (field (name "BOM_Manufacturer Part") "25121WJ0221T4E"))
      (libsource (lib "") (part "Unknown_895_545"))
    )
    (comp (ref "R151")
      (value "220Ω")
      (fields (field (name "BOM_Manufacturer Part") "25121WJ0221T4E"))
      (libsource (lib "") (part "Unknown_895_555"))
    )
    (comp (ref "R152")
      (value "220Ω")
      (fields (field (name "BOM_Manufacturer Part") "25121WJ0221T4E"))
      (libsource (lib "") (part "Unknown_895_565"))
    )
    (comp (ref "R153")
      (value "220Ω")
      (fields (field (name "BOM_Manufacturer Part") "25121WJ0221T4E"))
      (libsource (lib "") (part "Unknown_895_575"))
    )
    (comp (ref "R154")
      (value "220Ω")
      (fields (field (name "BOM_Manufacturer Part") "25121WJ0221T4E"))
      (libsource (lib "") (part "Unknown_135_1245"))
    )
    (comp (ref "R155")
      (value "220Ω")
      (fields (field (name "BOM_Manufacturer Part") "25121WJ0221T4E"))
      (libsource (lib "") (part "Unknown_135_1255"))
    )
    (comp (ref "R156")
      (value "220Ω")
      (fields (field (name "BOM_Manufacturer Part") "25121WJ0221T4E"))
      (libsource (lib "") (part "Unknown_135_1265"))
    )
    (comp (ref "R157")
      (value "220Ω")
      (fields (field (name "BOM_Manufacturer Part") "25121WJ0221T4E"))
      (libsource (lib "") (part "Unknown_135_1275"))
    )
    (comp (ref "R158")
      (value "220Ω")
      (fields (field (name "BOM_Manufacturer Part") "25121WJ0221T4E"))
      (libsource (lib "") (part "Unknown_135_1285"))
    )
    (comp (ref "R159")
      (value "220Ω")
      (fields (field (name "BOM_Manufacturer Part") "25121WJ0221T4E"))
      (libsource (lib "") (part "Unknown_135_1295"))
    )
    (comp (ref "R160")
      (value "220Ω")
      (fields (field (name "BOM_Manufacturer Part") "25121WJ0221T4E"))
      (libsource (lib "") (part "Unknown_135_1305"))
    )
    (comp (ref "R161")
      (value "220Ω")
      (fields (field (name "BOM_Manufacturer Part") "25121WJ0221T4E"))
      (libsource (lib "") (part "Unknown_135_1315"))
    )
    (comp (ref "R162")
      (value "220Ω")
      (fields (field (name "BOM_Manufacturer Part") "25121WJ0221T4E"))
      (libsource (lib "") (part "Unknown_395_910"))
    )
    (comp (ref "R163")
      (value "220Ω")
      (fields (field (name "BOM_Manufacturer Part") "25121WJ0221T4E"))
      (libsource (lib "") (part "Unknown_395_920"))
    )
    (comp (ref "R164")
      (value "220Ω")
      (fields (field (name "BOM_Manufacturer Part") "25121WJ0221T4E"))
      (libsource (lib "") (part "Unknown_395_930"))
    )
    (comp (ref "R165")
      (value "220Ω")
      (fields (field (name "BOM_Manufacturer Part") "25121WJ0221T4E"))
      (libsource (lib "") (part "Unknown_395_940"))
    )
    (comp (ref "R166")
      (value "220Ω")
      (fields (field (name "BOM_Manufacturer Part") "25121WJ0221T4E"))
      (libsource (lib "") (part "Unknown_395_950"))
    )
    (comp (ref "R167")
      (value "220Ω")
      (fields (field (name "BOM_Manufacturer Part") "25121WJ0221T4E"))
      (libsource (lib "") (part "Unknown_395_960"))
    )
    (comp (ref "R168")
      (value "220Ω")
      (fields (field (name "BOM_Manufacturer Part") "25121WJ0221T4E"))
      (libsource (lib "") (part "Unknown_395_970"))
    )
    (comp (ref "R169")
      (value "220Ω")
      (fields (field (name "BOM_Manufacturer Part") "25121WJ0221T4E"))
      (libsource (lib "") (part "Unknown_395_980"))
    )
    (comp (ref "R170")
      (value "220Ω")
      (fields (field (name "BOM_Manufacturer Part") "25121WJ0221T4E"))
      (libsource (lib "") (part "Unknown_395_1025"))
    )
    (comp (ref "R171")
      (value "220Ω")
      (fields (field (name "BOM_Manufacturer Part") "25121WJ0221T4E"))
      (libsource (lib "") (part "Unknown_395_1035"))
    )
    (comp (ref "R172")
      (value "220Ω")
      (fields (field (name "BOM_Manufacturer Part") "25121WJ0221T4E"))
      (libsource (lib "") (part "Unknown_395_1045"))
    )
    (comp (ref "R173")
      (value "220Ω")
      (fields (field (name "BOM_Manufacturer Part") "25121WJ0221T4E"))
      (libsource (lib "") (part "Unknown_395_1055"))
    )
    (comp (ref "R174")
      (value "220Ω")
      (fields (field (name "BOM_Manufacturer Part") "25121WJ0221T4E"))
      (libsource (lib "") (part "Unknown_395_1065"))
    )
    (comp (ref "R175")
      (value "220Ω")
      (fields (field (name "BOM_Manufacturer Part") "25121WJ0221T4E"))
      (libsource (lib "") (part "Unknown_395_1075"))
    )
    (comp (ref "R176")
      (value "220Ω")
      (fields (field (name "BOM_Manufacturer Part") "25121WJ0221T4E"))
      (libsource (lib "") (part "Unknown_395_1085"))
    )
    (comp (ref "R177")
      (value "220Ω")
      (fields (field (name "BOM_Manufacturer Part") "25121WJ0221T4E"))
      (libsource (lib "") (part "Unknown_395_1095"))
    )
    (comp (ref "R178")
      (value "220Ω")
      (fields (field (name "BOM_Manufacturer Part") "25121WJ0221T4E"))
      (libsource (lib "") (part "Unknown_395_1140"))
    )
    (comp (ref "R179")
      (value "220Ω")
      (fields (field (name "BOM_Manufacturer Part") "25121WJ0221T4E"))
      (libsource (lib "") (part "Unknown_395_1150"))
    )
    (comp (ref "R180")
      (value "220Ω")
      (fields (field (name "BOM_Manufacturer Part") "25121WJ0221T4E"))
      (libsource (lib "") (part "Unknown_395_1160"))
    )
    (comp (ref "R181")
      (value "220Ω")
      (fields (field (name "BOM_Manufacturer Part") "25121WJ0221T4E"))
      (libsource (lib "") (part "Unknown_395_1170"))
    )
    (comp (ref "R182")
      (value "220Ω")
      (fields (field (name "BOM_Manufacturer Part") "25121WJ0221T4E"))
      (libsource (lib "") (part "Unknown_395_1180"))
    )
    (comp (ref "R183")
      (value "220Ω")
      (fields (field (name "BOM_Manufacturer Part") "25121WJ0221T4E"))
      (libsource (lib "") (part "Unknown_395_1190"))
    )
    (comp (ref "R184")
      (value "220Ω")
      (fields (field (name "BOM_Manufacturer Part") "25121WJ0221T4E"))
      (libsource (lib "") (part "Unknown_395_1200"))
    )
    (comp (ref "R185")
      (value "220Ω")
      (fields (field (name "BOM_Manufacturer Part") "25121WJ0221T4E"))
      (libsource (lib "") (part "Unknown_395_1210"))
    )
    (comp (ref "R186")
      (value "220Ω")
      (fields (field (name "BOM_Manufacturer Part") "25121WJ0221T4E"))
      (libsource (lib "") (part "Unknown_395_1255"))
    )
    (comp (ref "R187")
      (value "220Ω")
      (fields (field (name "BOM_Manufacturer Part") "25121WJ0221T4E"))
      (libsource (lib "") (part "Unknown_395_1265"))
    )
    (comp (ref "R188")
      (value "220Ω")
      (fields (field (name "BOM_Manufacturer Part") "25121WJ0221T4E"))
      (libsource (lib "") (part "Unknown_395_1275"))
    )
    (comp (ref "R189")
      (value "220Ω")
      (fields (field (name "BOM_Manufacturer Part") "25121WJ0221T4E"))
      (libsource (lib "") (part "Unknown_395_1285"))
    )
    (comp (ref "R190")
      (value "220Ω")
      (fields (field (name "BOM_Manufacturer Part") "25121WJ0221T4E"))
      (libsource (lib "") (part "Unknown_395_1295"))
    )
    (comp (ref "R191")
      (value "220Ω")
      (fields (field (name "BOM_Manufacturer Part") "25121WJ0221T4E"))
      (libsource (lib "") (part "Unknown_395_1305"))
    )
    (comp (ref "R192")
      (value "220Ω")
      (fields (field (name "BOM_Manufacturer Part") "25121WJ0221T4E"))
      (libsource (lib "") (part "Unknown_395_1315"))
    )
    (comp (ref "R193")
      (value "220Ω")
      (fields (field (name "BOM_Manufacturer Part") "25121WJ0221T4E"))
      (libsource (lib "") (part "Unknown_395_1325"))
    )
    (comp (ref "R194")
      (value "1KΩ")
      (fields (field (name "BOM_Manufacturer Part") "25121WJ0102T4E"))
      (libsource (lib "") (part "Unknown_15_1525"))
    )
    (comp (ref "R195")
      (value "1KΩ")
      (fields (field (name "BOM_Manufacturer Part") "25121WJ0102T4E"))
      (libsource (lib "") (part "Unknown_100_1525"))
    )
    (comp (ref "R196")
      (value "1KΩ")
      (fields (field (name "BOM_Manufacturer Part") "25121WJ0102T4E"))
      (libsource (lib "") (part "Unknown_185_1525"))
    )
    (comp (ref "R197")
      (value "1KΩ")
      (fields (field (name "BOM_Manufacturer Part") "25121WJ0102T4E"))
      (libsource (lib "") (part "Unknown_275_1525"))
    )
    (comp (ref "R198")
      (value "1KΩ")
      (fields (field (name "BOM_Manufacturer Part") "25121WJ0102T4E"))
      (libsource (lib "") (part "Unknown_360_1525"))
    )
    (comp (ref "R199")
      (value "1KΩ")
      (fields (field (name "BOM_Manufacturer Part") "25121WJ0102T4E"))
      (libsource (lib "") (part "Unknown_445_1525"))
    )
    (comp (ref "R200")
      (value "1KΩ")
      (fields (field (name "BOM_Manufacturer Part") "25121WJ0102T4E"))
      (libsource (lib "") (part "Unknown_530_1525"))
    )
    (comp (ref "R201")
      (value "1KΩ")
      (fields (field (name "BOM_Manufacturer Part") "25121WJ0102T4E"))
      (libsource (lib "") (part "Unknown_615_1525"))
    )
    (comp (ref "ROT1")
      (value "SN74HC595")
      (fields (field (name "BOM_Manufacturer Part") "SN74HC595ANSR"))
      (libsource (lib "") (part "Unknown_175_165"))
    )
    (comp (ref "ROT2")
      (value "SN74HC595")
      (fields (field (name "BOM_Manufacturer Part") "SN74HC595ANSR"))
      (libsource (lib "") (part "Unknown_175_280"))
    )
    (comp (ref "ROT3")
      (value "SN74HC595")
      (fields (field (name "BOM_Manufacturer Part") "SN74HC595ANSR"))
      (libsource (lib "") (part "Unknown_175_395"))
    )
    (comp (ref "ROT4")
      (value "SN74HC595")
      (fields (field (name "BOM_Manufacturer Part") "SN74HC595ANSR"))
      (libsource (lib "") (part "Unknown_175_510"))
    )
    (comp (ref "ROT5")
      (value "SN74HC595")
      (fields (field (name "BOM_Manufacturer Part") "SN74HC595ANSR"))
      (libsource (lib "") (part "Unknown_435_175"))
    )
    (comp (ref "ROT6")
      (value "SN74HC595")
      (fields (field (name "BOM_Manufacturer Part") "SN74HC595ANSR"))
      (libsource (lib "") (part "Unknown_435_290"))
    )
    (comp (ref "ROT7")
      (value "SN74HC595")
      (fields (field (name "BOM_Manufacturer Part") "SN74HC595ANSR"))
      (libsource (lib "") (part "Unknown_435_405"))
    )
    (comp (ref "ROT8")
      (value "SN74HC595")
      (fields (field (name "BOM_Manufacturer Part") "SN74HC595ANSR"))
      (libsource (lib "") (part "Unknown_435_520"))
    )
  )
  (nets
    (net (code "1") (name "+5V") (class "Default")
      (node (ref "BLAU1") (pin "10") (pinfunction "SRCLR_10") (pintype "unspecified"))
      (node (ref "BLAU1") (pin "16") (pinfunction "VCC_16") (pintype "unspecified"))
      (node (ref "BLAU2") (pin "10") (pinfunction "SRCLR_10") (pintype "unspecified"))
      (node (ref "BLAU2") (pin "16") (pinfunction "VCC_16") (pintype "unspecified"))
      (node (ref "BLAU3") (pin "10") (pinfunction "SRCLR_10") (pintype "unspecified"))
      (node (ref "BLAU3") (pin "16") (pinfunction "VCC_16") (pintype "unspecified"))
      (node (ref "BLAU4") (pin "10") (pinfunction "SRCLR_10") (pintype "unspecified"))
      (node (ref "BLAU4") (pin "16") (pinfunction "VCC_16") (pintype "unspecified"))
      (node (ref "GRUEN1") (pin "10") (pinfunction "SRCLR_10") (pintype "unspecified"))
      (node (ref "GRUEN1") (pin "16") (pinfunction "VCC_16") (pintype "unspecified"))
      (node (ref "GRUEN2") (pin "10") (pinfunction "SRCLR_10") (pintype "unspecified"))
      (node (ref "GRUEN2") (pin "16") (pinfunction "VCC_16") (pintype "unspecified"))
      (node (ref "GRUEN3") (pin "10") (pinfunction "SRCLR_10") (pintype "unspecified"))
      (node (ref "GRUEN3") (pin "16") (pinfunction "VCC_16") (pintype "unspecified"))
      (node (ref "GRUEN4") (pin "10") (pinfunction "SRCLR_10") (pintype "unspecified"))
      (node (ref "GRUEN4") (pin "16") (pinfunction "VCC_16") (pintype "unspecified"))
      (node (ref "P1") (pin "2") (pinfunction "2_2") (pintype "input"))
      (node (ref "P12") (pin "4") (pinfunction "4_4") (pintype "input"))
      (node (ref "R20") (pin "2") (pinfunction "2_2") (pintype "input"))
      (node (ref "ROT1") (pin "10") (pinfunction "SRCLR_10") (pintype "unspecified"))
      (node (ref "ROT1") (pin "16") (pinfunction "VCC_16") (pintype "unspecified"))
      (node (ref "ROT2") (pin "10") (pinfunction "SRCLR_10") (pintype "unspecified"))
      (node (ref "ROT2") (pin "16") (pinfunction "VCC_16") (pintype "unspecified"))
      (node (ref "ROT3") (pin "10") (pinfunction "SRCLR_10") (pintype "unspecified"))
      (node (ref "ROT3") (pin "16") (pinfunction "VCC_16") (pintype "unspecified"))
      (node (ref "ROT4") (pin "10") (pinfunction "SRCLR_10") (pintype "unspecified"))
      (node (ref "ROT4") (pin "16") (pinfunction "VCC_16") (pintype "unspecified"))
    )
    (net (code "2") (name "/1") (class "Default")
      (node (ref "P27") (pin "1") (pinfunction "1_1") (pintype "input"))
      (node (ref "Q1") (pin "1") (pinfunction "G_1") (pintype "unspecified"))
      (node (ref "R194") (pin "2") (pinfunction "2_2") (pintype "input"))
    )
    (net (code "3") (name "/2") (class "Default")
      (node (ref "P27") (pin "2") (pinfunction "2_2") (pintype "input"))
      (node (ref "Q2") (pin "1") (pinfunction "G_1") (pintype "unspecified"))
      (node (ref "R195") (pin "2") (pinfunction "2_2") (pintype "input"))
    )
    (net (code "4") (name "/3") (class "Default")
      (node (ref "P27") (pin "3") (pinfunction "3_3") (pintype "input"))
      (node (ref "Q3") (pin "1") (pinfunction "G_1") (pintype "unspecified"))
      (node (ref "R196") (pin "2") (pinfunction "2_2") (pintype "input"))
    )
    (net (code "5") (name "/4") (class "Default")
      (node (ref "P27") (pin "4") (pinfunction "4_4") (pintype "input"))
      (node (ref "Q4") (pin "1") (pinfunction "G_1") (pintype "unspecified"))
      (node (ref "R197") (pin "2") (pinfunction "2_2") (pintype "input"))
    )
    (net (code "6") (name "/5") (class "Default")
      (node (ref "P27") (pin "5") (pinfunction "5_5") (pintype "input"))
      (node (ref "Q5") (pin "1") (pinfunction "G_1") (pintype "unspecified"))
      (node (ref "R198") (pin "2") (pinfunction "2_2") (pintype "input"))
    )
    (net (code "7") (name "/6") (class "Default")
      (node (ref "P27") (pin "6") (pinfunction "6_6") (pintype "input"))
      (node (ref "Q6") (pin "1") (pinfunction "G_1") (pintype "unspecified"))
      (node (ref "R199") (pin "2") (pinfunction "2_2") (pintype "input"))
    )
    (net (code "8") (name "/7") (class "Default")
      (node (ref "P27") (pin "7") (pinfunction "7_7") (pintype "input"))
      (node (ref "Q7") (pin "1") (pinfunction "G_1") (pintype "unspecified"))
      (node (ref "R200") (pin "2") (pinfunction "2_2") (pintype "input"))
    )
    (net (code "9") (name "/8") (class "Default")
      (node (ref "P27") (pin "8") (pinfunction "8_8") (pintype "input"))
      (node (ref "Q8") (pin "1") (pinfunction "G_1") (pintype "unspecified"))
      (node (ref "R201") (pin "2") (pinfunction "2_2") (pintype "input"))
    )
    (net (code "10") (name "/l1") (class "Default")
      (node (ref "P28") (pin "1") (pinfunction "1_1") (pintype "input"))
      (node (ref "Q1") (pin "2") (pinfunction "D_2") (pintype "unspecified"))
    )
    (net (code "11") (name "/l2") (class "Default")
      (node (ref "P28") (pin "2") (pinfunction "2_2") (pintype "input"))
      (node (ref "Q2") (pin "2") (pinfunction "D_2") (pintype "unspecified"))
    )
    (net (code "12") (name "/l3") (class "Default")
      (node (ref "P28") (pin "3") (pinfunction "3_3") (pintype "input"))
      (node (ref "Q3") (pin "2") (pinfunction "D_2") (pintype "unspecified"))
    )
    (net (code "13") (name "/l4") (class "Default")
      (node (ref "P28") (pin "4") (pinfunction "4_4") (pintype "input"))
      (node (ref "Q4") (pin "2") (pinfunction "D_2") (pintype "unspecified"))
    )
    (net (code "14") (name "/l5") (class "Default")
      (node (ref "P28") (pin "5") (pinfunction "5_5") (pintype "input"))
      (node (ref "Q5") (pin "2") (pinfunction "D_2") (pintype "unspecified"))
    )
    (net (code "15") (name "/l6") (class "Default")
      (node (ref "P28") (pin "6") (pinfunction "6_6") (pintype "input"))
      (node (ref "Q6") (pin "2") (pinfunction "D_2") (pintype "unspecified"))
    )
    (net (code "16") (name "/l7") (class "Default")
      (node (ref "P28") (pin "7") (pinfunction "7_7") (pintype "input"))
      (node (ref "Q7") (pin "2") (pinfunction "D_2") (pintype "unspecified"))
    )
    (net (code "17") (name "/l8") (class "Default")
      (node (ref "P28") (pin "8") (pinfunction "8_8") (pintype "input"))
      (node (ref "Q8") (pin "2") (pinfunction "D_2") (pintype "unspecified"))
    )
    (net (code "18") (name "GND") (class "Default")
      (node (ref "BLAU1") (pin "8") (pinfunction "GND_8") (pintype "unspecified"))
      (node (ref "BLAU2") (pin "8") (pinfunction "GND_8") (pintype "unspecified"))
      (node (ref "BLAU3") (pin "8") (pinfunction "GND_8") (pintype "unspecified"))
      (node (ref "BLAU4") (pin "8") (pinfunction "GND_8") (pintype "unspecified"))
      (node (ref "GRUEN1") (pin "8") (pinfunction "GND_8") (pintype "unspecified"))
      (node (ref "GRUEN2") (pin "8") (pinfunction "GND_8") (pintype "unspecified"))
      (node (ref "GRUEN3") (pin "8") (pinfunction "GND_8") (pintype "unspecified"))
      (node (ref "GRUEN4") (pin "8") (pinfunction "GND_8") (pintype "unspecified"))
      (node (ref "LED2") (pin "1") (pinfunction "K_1") (pintype "unspecified"))
      (node (ref "P1") (pin "1") (pinfunction "1_1") (pintype "input"))
      (node (ref "P12") (pin "5") (pinfunction "5_5") (pintype "input"))
      (node (ref "Q1") (pin "3") (pinfunction "S_3") (pintype "unspecified"))
      (node (ref "Q2") (pin "3") (pinfunction "S_3") (pintype "unspecified"))
      (node (ref "Q3") (pin "3") (pinfunction "S_3") (pintype "unspecified"))
      (node (ref "Q4") (pin "3") (pinfunction "S_3") (pintype "unspecified"))
      (node (ref "Q5") (pin "3") (pinfunction "S_3") (pintype "unspecified"))
      (node (ref "Q6") (pin "3") (pinfunction "S_3") (pintype "unspecified"))
      (node (ref "Q7") (pin "3") (pinfunction "S_3") (pintype "unspecified"))
      (node (ref "Q8") (pin "3") (pinfunction "S_3") (pintype "unspecified"))
      (node (ref "R194") (pin "1") (pinfunction "1_1") (pintype "input"))
      (node (ref "R195") (pin "1") (pinfunction "1_1") (pintype "input"))
      (node (ref "R196") (pin "1") (pinfunction "1_1") (pintype "input"))
      (node (ref "R197") (pin "1") (pinfunction "1_1") (pintype "input"))
      (node (ref "R198") (pin "1") (pinfunction "1_1") (pintype "input"))
      (node (ref "R199") (pin "1") (pinfunction "1_1") (pintype "input"))
      (node (ref "R200") (pin "1") (pinfunction "1_1") (pintype "input"))
      (node (ref "R201") (pin "1") (pinfunction "1_1") (pintype "input"))
      (node (ref "ROT1") (pin "13") (pinfunction "OE_13") (pintype "unspecified"))
      (node (ref "ROT1") (pin "8") (pinfunction "GND_8") (pintype "unspecified"))
      (node (ref "ROT2") (pin "13") (pinfunction "OE_13") (pintype "unspecified"))
      (node (ref "ROT2") (pin "8") (pinfunction "GND_8") (pintype "unspecified"))
      (node (ref "ROT3") (pin "13") (pinfunction "OE_13") (pintype "unspecified"))
      (node (ref "ROT3") (pin "8") (pinfunction "GND_8") (pintype "unspecified"))
      (node (ref "ROT4") (pin "13") (pinfunction "OE_13") (pintype "unspecified"))
      (node (ref "ROT4") (pin "8") (pinfunction "GND_8") (pintype "unspecified"))
    )
    (net (code "19") (name "Net-(BLAU1-OE)") (class "Default")
      (node (ref "BLAU1") (pin "13") (pinfunction "OE_13") (pintype "unspecified"))
      (node (ref "BLAU2") (pin "13") (pinfunction "OE_13") (pintype "unspecified"))
      (node (ref "BLAU3") (pin "13") (pinfunction "OE_13") (pintype "unspecified"))
      (node (ref "BLAU4") (pin "13") (pinfunction "OE_13") (pintype "unspecified"))
    )
    (net (code "20") (name "Net-(BLAU1-QA)") (class "Default")
      (node (ref "BLAU1") (pin "15") (pinfunction "QA_15") (pintype "unspecified"))
      (node (ref "R34") (pin "2") (pinfunction "2_2") (pintype "input"))
    )
    (net (code "21") (name "Net-(BLAU1-QB)") (class "Default")
      (node (ref "BLAU1") (pin "1") (pinfunction "QB_1") (pintype "unspecified"))
      (node (ref "R35") (pin "2") (pinfunction "2_2") (pintype "input"))
    )
    (net (code "22") (name "Net-(BLAU1-QC)") (class "Default")
      (node (ref "BLAU1") (pin "2") (pinfunction "QC_2") (pintype "unspecified"))
      (node (ref "R36") (pin "2") (pinfunction "2_2") (pintype "input"))
    )
    (net (code "23") (name "Net-(BLAU1-QD)") (class "Default")
      (node (ref "BLAU1") (pin "3") (pinfunction "QD_3") (pintype "unspecified"))
      (node (ref "R37") (pin "2") (pinfunction "2_2") (pintype "input"))
    )
    (net (code "24") (name "Net-(BLAU1-QE)") (class "Default")
      (node (ref "BLAU1") (pin "4") (pinfunction "QE_4") (pintype "unspecified"))
      (node (ref "R38") (pin "2") (pinfunction "2_2") (pintype "input"))
    )
    (net (code "25") (name "Net-(BLAU1-QF)") (class "Default")
      (node (ref "BLAU1") (pin "5") (pinfunction "QF_5") (pintype "unspecified"))
      (node (ref "R39") (pin "2") (pinfunction "2_2") (pintype "input"))
    )
    (net (code "26") (name "Net-(BLAU1-QG)") (class "Default")
      (node (ref "BLAU1") (pin "6") (pinfunction "QG_6") (pintype "unspecified"))
      (node (ref "R40") (pin "2") (pinfunction "2_2") (pintype "input"))
    )
    (net (code "27") (name "Net-(BLAU1-QH)") (class "Default")
      (node (ref "BLAU1") (pin "7") (pinfunction "QH_7") (pintype "unspecified"))
      (node (ref "R41") (pin "2") (pinfunction "2_2") (pintype "input"))
    )
    (net (code "28") (name "Net-(BLAU1-QH{slash}2)") (class "Default")
      (node (ref "BLAU1") (pin "9") (pinfunction "QH/2_9") (pintype "unspecified"))
      (node (ref "BLAU2") (pin "14") (pinfunction "SER_14") (pintype "unspecified"))
    )
    (net (code "29") (name "Net-(BLAU2-QA)") (class "Default")
      (node (ref "BLAU2") (pin "15") (pinfunction "QA_15") (pintype "unspecified"))
      (node (ref "R74") (pin "2") (pinfunction "2_2") (pintype "input"))
    )
    (net (code "30") (name "Net-(BLAU2-QB)") (class "Default")
      (node (ref "BLAU2") (pin "1") (pinfunction "QB_1") (pintype "unspecified"))
      (node (ref "R75") (pin "2") (pinfunction "2_2") (pintype "input"))
    )
    (net (code "31") (name "Net-(BLAU2-QC)") (class "Default")
      (node (ref "BLAU2") (pin "2") (pinfunction "QC_2") (pintype "unspecified"))
      (node (ref "R76") (pin "2") (pinfunction "2_2") (pintype "input"))
    )
    (net (code "32") (name "Net-(BLAU2-QD)") (class "Default")
      (node (ref "BLAU2") (pin "3") (pinfunction "QD_3") (pintype "unspecified"))
      (node (ref "R77") (pin "2") (pinfunction "2_2") (pintype "input"))
    )
    (net (code "33") (name "Net-(BLAU2-QE)") (class "Default")
      (node (ref "BLAU2") (pin "4") (pinfunction "QE_4") (pintype "unspecified"))
      (node (ref "R78") (pin "2") (pinfunction "2_2") (pintype "input"))
    )
    (net (code "34") (name "Net-(BLAU2-QF)") (class "Default")
      (node (ref "BLAU2") (pin "5") (pinfunction "QF_5") (pintype "unspecified"))
      (node (ref "R79") (pin "2") (pinfunction "2_2") (pintype "input"))
    )
    (net (code "35") (name "Net-(BLAU2-QG)") (class "Default")
      (node (ref "BLAU2") (pin "6") (pinfunction "QG_6") (pintype "unspecified"))
      (node (ref "R80") (pin "2") (pinfunction "2_2") (pintype "input"))
    )
    (net (code "36") (name "Net-(BLAU2-QH)") (class "Default")
      (node (ref "BLAU2") (pin "7") (pinfunction "QH_7") (pintype "unspecified"))
      (node (ref "R81") (pin "2") (pinfunction "2_2") (pintype "input"))
    )
    (net (code "37") (name "Net-(BLAU2-QH{slash}2)") (class "Default")
      (node (ref "BLAU2") (pin "9") (pinfunction "QH/2_9") (pintype "unspecified"))
      (node (ref "BLAU3") (pin "14") (pinfunction "SER_14") (pintype "unspecified"))
    )
    (net (code "38") (name "Net-(BLAU3-QA)") (class "Default")
      (node (ref "BLAU3") (pin "15") (pinfunction "QA_15") (pintype "unspecified"))
      (node (ref "R114") (pin "2") (pinfunction "2_2") (pintype "input"))
    )
    (net (code "39") (name "Net-(BLAU3-QB)") (class "Default")
      (node (ref "BLAU3") (pin "1") (pinfunction "QB_1") (pintype "unspecified"))
      (node (ref "R115") (pin "2") (pinfunction "2_2") (pintype "input"))
    )
    (net (code "40") (name "Net-(BLAU3-QC)") (class "Default")
      (node (ref "BLAU3") (pin "2") (pinfunction "QC_2") (pintype "unspecified"))
      (node (ref "R116") (pin "2") (pinfunction "2_2") (pintype "input"))
    )
    (net (code "41") (name "Net-(BLAU3-QD)") (class "Default")
      (node (ref "BLAU3") (pin "3") (pinfunction "QD_3") (pintype "unspecified"))
      (node (ref "R117") (pin "2") (pinfunction "2_2") (pintype "input"))
    )
    (net (code "42") (name "Net-(BLAU3-QE)") (class "Default")
      (node (ref "BLAU3") (pin "4") (pinfunction "QE_4") (pintype "unspecified"))
      (node (ref "R118") (pin "2") (pinfunction "2_2") (pintype "input"))
    )
    (net (code "43") (name "Net-(BLAU3-QF)") (class "Default")
      (node (ref "BLAU3") (pin "5") (pinfunction "QF_5") (pintype "unspecified"))
      (node (ref "R119") (pin "2") (pinfunction "2_2") (pintype "input"))
    )
    (net (code "44") (name "Net-(BLAU3-QG)") (class "Default")
      (node (ref "BLAU3") (pin "6") (pinfunction "QG_6") (pintype "unspecified"))
      (node (ref "R120") (pin "2") (pinfunction "2_2") (pintype "input"))
    )
    (net (code "45") (name "Net-(BLAU3-QH)") (class "Default")
      (node (ref "BLAU3") (pin "7") (pinfunction "QH_7") (pintype "unspecified"))
      (node (ref "R121") (pin "2") (pinfunction "2_2") (pintype "input"))
    )
    (net (code "46") (name "Net-(BLAU3-QH{slash}2)") (class "Default")
      (node (ref "BLAU3") (pin "9") (pinfunction "QH/2_9") (pintype "unspecified"))
      (node (ref "BLAU4") (pin "14") (pinfunction "SER_14") (pintype "unspecified"))
    )
    (net (code "47") (name "Net-(BLAU4-QA)") (class "Default")
      (node (ref "BLAU4") (pin "15") (pinfunction "QA_15") (pintype "unspecified"))
      (node (ref "R154") (pin "2") (pinfunction "2_2") (pintype "input"))
    )
    (net (code "48") (name "Net-(BLAU4-QB)") (class "Default")
      (node (ref "BLAU4") (pin "1") (pinfunction "QB_1") (pintype "unspecified"))
      (node (ref "R155") (pin "2") (pinfunction "2_2") (pintype "input"))
    )
    (net (code "49") (name "Net-(BLAU4-QC)") (class "Default")
      (node (ref "BLAU4") (pin "2") (pinfunction "QC_2") (pintype "unspecified"))
      (node (ref "R156") (pin "2") (pinfunction "2_2") (pintype "input"))
    )
    (net (code "50") (name "Net-(BLAU4-QD)") (class "Default")
      (node (ref "BLAU4") (pin "3") (pinfunction "QD_3") (pintype "unspecified"))
      (node (ref "R157") (pin "2") (pinfunction "2_2") (pintype "input"))
    )
    (net (code "51") (name "Net-(BLAU4-QE)") (class "Default")
      (node (ref "BLAU4") (pin "4") (pinfunction "QE_4") (pintype "unspecified"))
      (node (ref "R158") (pin "2") (pinfunction "2_2") (pintype "input"))
    )
    (net (code "52") (name "Net-(BLAU4-QF)") (class "Default")
      (node (ref "BLAU4") (pin "5") (pinfunction "QF_5") (pintype "unspecified"))
      (node (ref "R159") (pin "2") (pinfunction "2_2") (pintype "input"))
    )
    (net (code "53") (name "Net-(BLAU4-QG)") (class "Default")
      (node (ref "BLAU4") (pin "6") (pinfunction "QG_6") (pintype "unspecified"))
      (node (ref "R160") (pin "2") (pinfunction "2_2") (pintype "input"))
    )
    (net (code "54") (name "Net-(BLAU4-QH)") (class "Default")
      (node (ref "BLAU4") (pin "7") (pinfunction "QH_7") (pintype "unspecified"))
      (node (ref "R161") (pin "2") (pinfunction "2_2") (pintype "input"))
    )
    (net (code "55") (name "Net-(BLAU4-QH{slash}2)") (class "Default")
      (node (ref "BLAU4") (pin "9") (pinfunction "QH/2_9") (pintype "unspecified"))
      (node (ref "BLAU5") (pin "14") (pinfunction "SER_14") (pintype "unspecified"))
    )
    (net (code "56") (name "Net-(BLAU5-GND)") (class "Default")
      (node (ref "BLAU5") (pin "13") (pinfunction "OE_13") (pintype "unspecified"))
      (node (ref "BLAU5") (pin "8") (pinfunction "GND_8") (pintype "unspecified"))
      (node (ref "BLAU6") (pin "13") (pinfunction "OE_13") (pintype "unspecified"))
      (node (ref "BLAU6") (pin "8") (pinfunction "GND_8") (pintype "unspecified"))
      (node (ref "BLAU7") (pin "13") (pinfunction "OE_13") (pintype "unspecified"))
      (node (ref "BLAU7") (pin "8") (pinfunction "GND_8") (pintype "unspecified"))
      (node (ref "BLAU8") (pin "13") (pinfunction "OE_13") (pintype "unspecified"))
      (node (ref "BLAU8") (pin "8") (pinfunction "GND_8") (pintype "unspecified"))
    )
    (net (code "57") (name "Net-(BLAU5-QA)") (class "Default")
      (node (ref "BLAU5") (pin "10") (pinfunction "SRCLR_10") (pintype "unspecified"))
      (node (ref "BLAU5") (pin "15") (pinfunction "QA_15") (pintype "unspecified"))
      (node (ref "BLAU5") (pin "16") (pinfunction "VCC_16") (pintype "unspecified"))
      (node (ref "BLAU6") (pin "10") (pinfunction "SRCLR_10") (pintype "unspecified"))
      (node (ref "BLAU6") (pin "16") (pinfunction "VCC_16") (pintype "unspecified"))
      (node (ref "BLAU7") (pin "10") (pinfunction "SRCLR_10") (pintype "unspecified"))
      (node (ref "BLAU7") (pin "15") (pinfunction "QA_15") (pintype "unspecified"))
      (node (ref "BLAU7") (pin "16") (pinfunction "VCC_16") (pintype "unspecified"))
      (node (ref "BLAU8") (pin "10") (pinfunction "SRCLR_10") (pintype "unspecified"))
      (node (ref "BLAU8") (pin "16") (pinfunction "VCC_16") (pintype "unspecified"))
      (node (ref "R162") (pin "2") (pinfunction "2_2") (pintype "input"))
      (node (ref "R178") (pin "2") (pinfunction "2_2") (pintype "input"))
    )
    (net (code "58") (name "Net-(BLAU5-QB)") (class "Default")
      (node (ref "BLAU5") (pin "1") (pinfunction "QB_1") (pintype "unspecified"))
      (node (ref "R163") (pin "2") (pinfunction "2_2") (pintype "input"))
    )
    (net (code "59") (name "Net-(BLAU5-QC)") (class "Default")
      (node (ref "BLAU5") (pin "2") (pinfunction "QC_2") (pintype "unspecified"))
      (node (ref "R164") (pin "2") (pinfunction "2_2") (pintype "input"))
    )
    (net (code "60") (name "Net-(BLAU5-QD)") (class "Default")
      (node (ref "BLAU5") (pin "3") (pinfunction "QD_3") (pintype "unspecified"))
      (node (ref "R165") (pin "2") (pinfunction "2_2") (pintype "input"))
    )
    (net (code "61") (name "Net-(BLAU5-QE)") (class "Default")
      (node (ref "BLAU5") (pin "4") (pinfunction "QE_4") (pintype "unspecified"))
      (node (ref "R166") (pin "2") (pinfunction "2_2") (pintype "input"))
    )
    (net (code "62") (name "Net-(BLAU5-QF)") (class "Default")
      (node (ref "BLAU5") (pin "5") (pinfunction "QF_5") (pintype "unspecified"))
      (node (ref "R167") (pin "2") (pinfunction "2_2") (pintype "input"))
    )
    (net (code "63") (name "Net-(BLAU5-QG)") (class "Default")
      (node (ref "BLAU5") (pin "6") (pinfunction "QG_6") (pintype "unspecified"))
      (node (ref "R168") (pin "2") (pinfunction "2_2") (pintype "input"))
    )
    (net (code "64") (name "Net-(BLAU5-QH)") (class "Default")
      (node (ref "BLAU5") (pin "7") (pinfunction "QH_7") (pintype "unspecified"))
      (node (ref "R169") (pin "2") (pinfunction "2_2") (pintype "input"))
    )
    (net (code "65") (name "Net-(BLAU5-QH{slash}2)") (class "Default")
      (node (ref "BLAU5") (pin "9") (pinfunction "QH/2_9") (pintype "unspecified"))
      (node (ref "BLAU6") (pin "14") (pinfunction "SER_14") (pintype "unspecified"))
    )
    (net (code "66") (name "Net-(BLAU5-RCLK)") (class "Default")
      (node (ref "BLAU5") (pin "12") (pinfunction "RCLK_12") (pintype "unspecified"))
      (node (ref "BLAU6") (pin "12") (pinfunction "RCLK_12") (pintype "unspecified"))
      (node (ref "BLAU7") (pin "12") (pinfunction "RCLK_12") (pintype "unspecified"))
      (node (ref "BLAU8") (pin "12") (pinfunction "RCLK_12") (pintype "unspecified"))
    )
    (net (code "67") (name "Net-(BLAU5-SRCLK)") (class "Default")
      (node (ref "BLAU5") (pin "11") (pinfunction "SRCLK_11") (pintype "unspecified"))
      (node (ref "BLAU6") (pin "11") (pinfunction "SRCLK_11") (pintype "unspecified"))
      (node (ref "BLAU7") (pin "11") (pinfunction "SRCLK_11") (pintype "unspecified"))
      (node (ref "BLAU8") (pin "11") (pinfunction "SRCLK_11") (pintype "unspecified"))
    )
    (net (code "68") (name "Net-(BLAU6-QA)") (class "Default")
      (node (ref "BLAU6") (pin "15") (pinfunction "QA_15") (pintype "unspecified"))
      (node (ref "R170") (pin "2") (pinfunction "2_2") (pintype "input"))
    )
    (net (code "69") (name "Net-(BLAU6-QB)") (class "Default")
      (node (ref "BLAU6") (pin "1") (pinfunction "QB_1") (pintype "unspecified"))
      (node (ref "R171") (pin "2") (pinfunction "2_2") (pintype "input"))
    )
    (net (code "70") (name "Net-(BLAU6-QC)") (class "Default")
      (node (ref "BLAU6") (pin "2") (pinfunction "QC_2") (pintype "unspecified"))
      (node (ref "R172") (pin "2") (pinfunction "2_2") (pintype "input"))
    )
    (net (code "71") (name "Net-(BLAU6-QD)") (class "Default")
      (node (ref "BLAU6") (pin "3") (pinfunction "QD_3") (pintype "unspecified"))
      (node (ref "R173") (pin "2") (pinfunction "2_2") (pintype "input"))
    )
    (net (code "72") (name "Net-(BLAU6-QE)") (class "Default")
      (node (ref "BLAU6") (pin "4") (pinfunction "QE_4") (pintype "unspecified"))
      (node (ref "R174") (pin "2") (pinfunction "2_2") (pintype "input"))
    )
    (net (code "73") (name "Net-(BLAU6-QF)") (class "Default")
      (node (ref "BLAU6") (pin "5") (pinfunction "QF_5") (pintype "unspecified"))
      (node (ref "R175") (pin "2") (pinfunction "2_2") (pintype "input"))
    )
    (net (code "74") (name "Net-(BLAU6-QG)") (class "Default")
      (node (ref "BLAU6") (pin "6") (pinfunction "QG_6") (pintype "unspecified"))
      (node (ref "R176") (pin "2") (pinfunction "2_2") (pintype "input"))
    )
    (net (code "75") (name "Net-(BLAU6-QH)") (class "Default")
      (node (ref "BLAU6") (pin "7") (pinfunction "QH_7") (pintype "unspecified"))
      (node (ref "R177") (pin "2") (pinfunction "2_2") (pintype "input"))
    )
    (net (code "76") (name "Net-(BLAU6-QH{slash}2)") (class "Default")
      (node (ref "BLAU6") (pin "9") (pinfunction "QH/2_9") (pintype "unspecified"))
      (node (ref "BLAU7") (pin "14") (pinfunction "SER_14") (pintype "unspecified"))
    )
    (net (code "77") (name "Net-(BLAU7-QB)") (class "Default")
      (node (ref "BLAU7") (pin "1") (pinfunction "QB_1") (pintype "unspecified"))
      (node (ref "R179") (pin "2") (pinfunction "2_2") (pintype "input"))
    )
    (net (code "78") (name "Net-(BLAU7-QC)") (class "Default")
      (node (ref "BLAU7") (pin "2") (pinfunction "QC_2") (pintype "unspecified"))
      (node (ref "R180") (pin "2") (pinfunction "2_2") (pintype "input"))
    )
    (net (code "79") (name "Net-(BLAU7-QD)") (class "Default")
      (node (ref "BLAU7") (pin "3") (pinfunction "QD_3") (pintype "unspecified"))
      (node (ref "R181") (pin "2") (pinfunction "2_2") (pintype "input"))
    )
    (net (code "80") (name "Net-(BLAU7-QE)") (class "Default")
      (node (ref "BLAU7") (pin "4") (pinfunction "QE_4") (pintype "unspecified"))
      (node (ref "R182") (pin "2") (pinfunction "2_2") (pintype "input"))
    )
    (net (code "81") (name "Net-(BLAU7-QF)") (class "Default")
      (node (ref "BLAU7") (pin "5") (pinfunction "QF_5") (pintype "unspecified"))
      (node (ref "R183") (pin "2") (pinfunction "2_2") (pintype "input"))
    )
    (net (code "82") (name "Net-(BLAU7-QG)") (class "Default")
      (node (ref "BLAU7") (pin "6") (pinfunction "QG_6") (pintype "unspecified"))
      (node (ref "R184") (pin "2") (pinfunction "2_2") (pintype "input"))
    )
    (net (code "83") (name "Net-(BLAU7-QH)") (class "Default")
      (node (ref "BLAU7") (pin "7") (pinfunction "QH_7") (pintype "unspecified"))
      (node (ref "R185") (pin "2") (pinfunction "2_2") (pintype "input"))
    )
    (net (code "84") (name "Net-(BLAU7-QH{slash}2)") (class "Default")
      (node (ref "BLAU7") (pin "9") (pinfunction "QH/2_9") (pintype "unspecified"))
      (node (ref "BLAU8") (pin "14") (pinfunction "SER_14") (pintype "unspecified"))
    )
    (net (code "85") (name "Net-(BLAU8-QA)") (class "Default")
      (node (ref "BLAU8") (pin "15") (pinfunction "QA_15") (pintype "unspecified"))
      (node (ref "R186") (pin "2") (pinfunction "2_2") (pintype "input"))
    )
    (net (code "86") (name "Net-(BLAU8-QB)") (class "Default")
      (node (ref "BLAU8") (pin "1") (pinfunction "QB_1") (pintype "unspecified"))
      (node (ref "R187") (pin "2") (pinfunction "2_2") (pintype "input"))
    )
    (net (code "87") (name "Net-(BLAU8-QC)") (class "Default")
      (node (ref "BLAU8") (pin "2") (pinfunction "QC_2") (pintype "unspecified"))
      (node (ref "R188") (pin "2") (pinfunction "2_2") (pintype "input"))
    )
    (net (code "88") (name "Net-(BLAU8-QD)") (class "Default")
      (node (ref "BLAU8") (pin "3") (pinfunction "QD_3") (pintype "unspecified"))
      (node (ref "R189") (pin "2") (pinfunction "2_2") (pintype "input"))
    )
    (net (code "89") (name "Net-(BLAU8-QE)") (class "Default")
      (node (ref "BLAU8") (pin "4") (pinfunction "QE_4") (pintype "unspecified"))
      (node (ref "R190") (pin "2") (pinfunction "2_2") (pintype "input"))
    )
    (net (code "90") (name "Net-(BLAU8-QF)") (class "Default")
      (node (ref "BLAU8") (pin "5") (pinfunction "QF_5") (pintype "unspecified"))
      (node (ref "R191") (pin "2") (pinfunction "2_2") (pintype "input"))
    )
    (net (code "91") (name "Net-(BLAU8-QG)") (class "Default")
      (node (ref "BLAU8") (pin "6") (pinfunction "QG_6") (pintype "unspecified"))
      (node (ref "R192") (pin "2") (pinfunction "2_2") (pintype "input"))
    )
    (net (code "92") (name "Net-(BLAU8-QH)") (class "Default")
      (node (ref "BLAU8") (pin "7") (pinfunction "QH_7") (pintype "unspecified"))
      (node (ref "R193") (pin "2") (pinfunction "2_2") (pintype "input"))
    )
    (net (code "93") (name "Net-(GRUEN1-OE)") (class "Default")
      (node (ref "GRUEN1") (pin "13") (pinfunction "OE_13") (pintype "unspecified"))
      (node (ref "GRUEN2") (pin "13") (pinfunction "OE_13") (pintype "unspecified"))
      (node (ref "GRUEN3") (pin "13") (pinfunction "OE_13") (pintype "unspecified"))
      (node (ref "GRUEN4") (pin "13") (pinfunction "OE_13") (pintype "unspecified"))
    )
    (net (code "94") (name "Net-(GRUEN1-QA)") (class "Default")
      (node (ref "GRUEN1") (pin "15") (pinfunction "QA_15") (pintype "unspecified"))
      (node (ref "R82") (pin "2") (pinfunction "2_2") (pintype "input"))
    )
    (net (code "95") (name "Net-(GRUEN1-QB)") (class "Default")
      (node (ref "GRUEN1") (pin "1") (pinfunction "QB_1") (pintype "unspecified"))
      (node (ref "R83") (pin "2") (pinfunction "2_2") (pintype "input"))
    )
    (net (code "96") (name "Net-(GRUEN1-QC)") (class "Default")
      (node (ref "GRUEN1") (pin "2") (pinfunction "QC_2") (pintype "unspecified"))
      (node (ref "R84") (pin "2") (pinfunction "2_2") (pintype "input"))
    )
    (net (code "97") (name "Net-(GRUEN1-QD)") (class "Default")
      (node (ref "GRUEN1") (pin "3") (pinfunction "QD_3") (pintype "unspecified"))
      (node (ref "R85") (pin "2") (pinfunction "2_2") (pintype "input"))
    )
    (net (code "98") (name "Net-(GRUEN1-QE)") (class "Default")
      (node (ref "GRUEN1") (pin "4") (pinfunction "QE_4") (pintype "unspecified"))
      (node (ref "R86") (pin "2") (pinfunction "2_2") (pintype "input"))
    )
    (net (code "99") (name "Net-(GRUEN1-QF)") (class "Default")
      (node (ref "GRUEN1") (pin "5") (pinfunction "QF_5") (pintype "unspecified"))
      (node (ref "R87") (pin "2") (pinfunction "2_2") (pintype "input"))
    )
    (net (code "100") (name "Net-(GRUEN1-QG)") (class "Default")
      (node (ref "GRUEN1") (pin "6") (pinfunction "QG_6") (pintype "unspecified"))
      (node (ref "R88") (pin "2") (pinfunction "2_2") (pintype "input"))
    )
    (net (code "101") (name "Net-(GRUEN1-QH)") (class "Default")
      (node (ref "GRUEN1") (pin "7") (pinfunction "QH_7") (pintype "unspecified"))
      (node (ref "R89") (pin "2") (pinfunction "2_2") (pintype "input"))
    )
    (net (code "102") (name "Net-(GRUEN1-QH{slash}2)") (class "Default")
      (node (ref "GRUEN1") (pin "9") (pinfunction "QH/2_9") (pintype "unspecified"))
      (node (ref "GRUEN2") (pin "14") (pinfunction "SER_14") (pintype "unspecified"))
    )
    (net (code "103") (name "Net-(GRUEN1-SER)") (class "Default")
      (node (ref "GRUEN1") (pin "14") (pinfunction "SER_14") (pintype "unspecified"))
      (node (ref "ROT8") (pin "9") (pinfunction "QH/2_9") (pintype "unspecified"))
    )
    (net (code "104") (name "Net-(GRUEN2-QA)") (class "Default")
      (node (ref "GRUEN2") (pin "15") (pinfunction "QA_15") (pintype "unspecified"))
      (node (ref "R90") (pin "2") (pinfunction "2_2") (pintype "input"))
    )
    (net (code "105") (name "Net-(GRUEN2-QB)") (class "Default")
      (node (ref "GRUEN2") (pin "1") (pinfunction "QB_1") (pintype "unspecified"))
      (node (ref "R91") (pin "2") (pinfunction "2_2") (pintype "input"))
    )
    (net (code "106") (name "Net-(GRUEN2-QC)") (class "Default")
      (node (ref "GRUEN2") (pin "2") (pinfunction "QC_2") (pintype "unspecified"))
      (node (ref "R92") (pin "2") (pinfunction "2_2") (pintype "input"))
    )
    (net (code "107") (name "Net-(GRUEN2-QD)") (class "Default")
      (node (ref "GRUEN2") (pin "3") (pinfunction "QD_3") (pintype "unspecified"))
      (node (ref "R93") (pin "2") (pinfunction "2_2") (pintype "input"))
    )
    (net (code "108") (name "Net-(GRUEN2-QE)") (class "Default")
      (node (ref "GRUEN2") (pin "4") (pinfunction "QE_4") (pintype "unspecified"))
      (node (ref "R94") (pin "2") (pinfunction "2_2") (pintype "input"))
    )
    (net (code "109") (name "Net-(GRUEN2-QF)") (class "Default")
      (node (ref "GRUEN2") (pin "5") (pinfunction "QF_5") (pintype "unspecified"))
      (node (ref "R95") (pin "2") (pinfunction "2_2") (pintype "input"))
    )
    (net (code "110") (name "Net-(GRUEN2-QG)") (class "Default")
      (node (ref "GRUEN2") (pin "6") (pinfunction "QG_6") (pintype "unspecified"))
      (node (ref "R96") (pin "2") (pinfunction "2_2") (pintype "input"))
    )
    (net (code "111") (name "Net-(GRUEN2-QH)") (class "Default")
      (node (ref "GRUEN2") (pin "7") (pinfunction "QH_7") (pintype "unspecified"))
      (node (ref "R97") (pin "2") (pinfunction "2_2") (pintype "input"))
    )
    (net (code "112") (name "Net-(GRUEN2-QH{slash}2)") (class "Default")
      (node (ref "GRUEN2") (pin "9") (pinfunction "QH/2_9") (pintype "unspecified"))
      (node (ref "GRUEN3") (pin "14") (pinfunction "SER_14") (pintype "unspecified"))
    )
    (net (code "113") (name "Net-(GRUEN3-QA)") (class "Default")
      (node (ref "GRUEN3") (pin "15") (pinfunction "QA_15") (pintype "unspecified"))
      (node (ref "R98") (pin "2") (pinfunction "2_2") (pintype "input"))
    )
    (net (code "114") (name "Net-(GRUEN3-QB)") (class "Default")
      (node (ref "GRUEN3") (pin "1") (pinfunction "QB_1") (pintype "unspecified"))
      (node (ref "R99") (pin "2") (pinfunction "2_2") (pintype "input"))
    )
    (net (code "115") (name "Net-(GRUEN3-QC)") (class "Default")
      (node (ref "GRUEN3") (pin "2") (pinfunction "QC_2") (pintype "unspecified"))
      (node (ref "R100") (pin "2") (pinfunction "2_2") (pintype "input"))
    )
    (net (code "116") (name "Net-(GRUEN3-QD)") (class "Default")
      (node (ref "GRUEN3") (pin "3") (pinfunction "QD_3") (pintype "unspecified"))
      (node (ref "R101") (pin "2") (pinfunction "2_2") (pintype "input"))
    )
    (net (code "117") (name "Net-(GRUEN3-QE)") (class "Default")
      (node (ref "GRUEN3") (pin "4") (pinfunction "QE_4") (pintype "unspecified"))
      (node (ref "R102") (pin "2") (pinfunction "2_2") (pintype "input"))
    )
    (net (code "118") (name "Net-(GRUEN3-QF)") (class "Default")
      (node (ref "GRUEN3") (pin "5") (pinfunction "QF_5") (pintype "unspecified"))
      (node (ref "R103") (pin "2") (pinfunction "2_2") (pintype "input"))
    )
    (net (code "119") (name "Net-(GRUEN3-QG)") (class "Default")
      (node (ref "GRUEN3") (pin "6") (pinfunction "QG_6") (pintype "unspecified"))
      (node (ref "R104") (pin "2") (pinfunction "2_2") (pintype "input"))
    )
    (net (code "120") (name "Net-(GRUEN3-QH)") (class "Default")
      (node (ref "GRUEN3") (pin "7") (pinfunction "QH_7") (pintype "unspecified"))
      (node (ref "R105") (pin "2") (pinfunction "2_2") (pintype "input"))
    )
    (net (code "121") (name "Net-(GRUEN3-QH{slash}2)") (class "Default")
      (node (ref "GRUEN3") (pin "9") (pinfunction "QH/2_9") (pintype "unspecified"))
      (node (ref "GRUEN4") (pin "14") (pinfunction "SER_14") (pintype "unspecified"))
    )
    (net (code "122") (name "Net-(GRUEN4-QA)") (class "Default")
      (node (ref "GRUEN4") (pin "15") (pinfunction "QA_15") (pintype "unspecified"))
      (node (ref "R106") (pin "2") (pinfunction "2_2") (pintype "input"))
    )
    (net (code "123") (name "Net-(GRUEN4-QB)") (class "Default")
      (node (ref "GRUEN4") (pin "1") (pinfunction "QB_1") (pintype "unspecified"))
      (node (ref "R107") (pin "2") (pinfunction "2_2") (pintype "input"))
    )
    (net (code "124") (name "Net-(GRUEN4-QC)") (class "Default")
      (node (ref "GRUEN4") (pin "2") (pinfunction "QC_2") (pintype "unspecified"))
      (node (ref "R108") (pin "2") (pinfunction "2_2") (pintype "input"))
    )
    (net (code "125") (name "Net-(GRUEN4-QD)") (class "Default")
      (node (ref "GRUEN4") (pin "3") (pinfunction "QD_3") (pintype "unspecified"))
      (node (ref "R109") (pin "2") (pinfunction "2_2") (pintype "input"))
    )
    (net (code "126") (name "Net-(GRUEN4-QE)") (class "Default")
      (node (ref "GRUEN4") (pin "4") (pinfunction "QE_4") (pintype "unspecified"))
      (node (ref "R110") (pin "2") (pinfunction "2_2") (pintype "input"))
    )
    (net (code "127") (name "Net-(GRUEN4-QF)") (class "Default")
      (node (ref "GRUEN4") (pin "5") (pinfunction "QF_5") (pintype "unspecified"))
      (node (ref "R111") (pin "2") (pinfunction "2_2") (pintype "input"))
    )
    (net (code "128") (name "Net-(GRUEN4-QG)") (class "Default")
      (node (ref "GRUEN4") (pin "6") (pinfunction "QG_6") (pintype "unspecified"))
      (node (ref "R112") (pin "2") (pinfunction "2_2") (pintype "input"))
    )
    (net (code "129") (name "Net-(GRUEN4-QH)") (class "Default")
      (node (ref "GRUEN4") (pin "7") (pinfunction "QH_7") (pintype "unspecified"))
      (node (ref "R113") (pin "2") (pinfunction "2_2") (pintype "input"))
    )
    (net (code "130") (name "Net-(GRUEN4-QH{slash}2)") (class "Default")
      (node (ref "GRUEN4") (pin "9") (pinfunction "QH/2_9") (pintype "unspecified"))
      (node (ref "GRUEN5") (pin "14") (pinfunction "SER_14") (pintype "unspecified"))
    )
    (net (code "131") (name "Net-(GRUEN5-GND)") (class "Default")
      (node (ref "GRUEN5") (pin "13") (pinfunction "OE_13") (pintype "unspecified"))
      (node (ref "GRUEN5") (pin "8") (pinfunction "GND_8") (pintype "unspecified"))
      (node (ref "GRUEN6") (pin "13") (pinfunction "OE_13") (pintype "unspecified"))
      (node (ref "GRUEN6") (pin "8") (pinfunction "GND_8") (pintype "unspecified"))
      (node (ref "GRUEN7") (pin "13") (pinfunction "OE_13") (pintype "unspecified"))
      (node (ref "GRUEN7") (pin "8") (pinfunction "GND_8") (pintype "unspecified"))
      (node (ref "GRUEN8") (pin "13") (pinfunction "OE_13") (pintype "unspecified"))
      (node (ref "GRUEN8") (pin "8") (pinfunction "GND_8") (pintype "unspecified"))
    )
    (net (code "132") (name "Net-(GRUEN5-QA)") (class "Default")
      (node (ref "GRUEN5") (pin "10") (pinfunction "SRCLR_10") (pintype "unspecified"))
      (node (ref "GRUEN5") (pin "15") (pinfunction "QA_15") (pintype "unspecified"))
      (node (ref "GRUEN5") (pin "16") (pinfunction "VCC_16") (pintype "unspecified"))
      (node (ref "GRUEN6") (pin "10") (pinfunction "SRCLR_10") (pintype "unspecified"))
      (node (ref "GRUEN6") (pin "16") (pinfunction "VCC_16") (pintype "unspecified"))
      (node (ref "GRUEN7") (pin "10") (pinfunction "SRCLR_10") (pintype "unspecified"))
      (node (ref "GRUEN7") (pin "15") (pinfunction "QA_15") (pintype "unspecified"))
      (node (ref "GRUEN7") (pin "16") (pinfunction "VCC_16") (pintype "unspecified"))
      (node (ref "GRUEN8") (pin "10") (pinfunction "SRCLR_10") (pintype "unspecified"))
      (node (ref "GRUEN8") (pin "16") (pinfunction "VCC_16") (pintype "unspecified"))
      (node (ref "R122") (pin "2") (pinfunction "2_2") (pintype "input"))
      (node (ref "R138") (pin "2") (pinfunction "2_2") (pintype "input"))
    )
    (net (code "133") (name "Net-(GRUEN5-QB)") (class "Default")
      (node (ref "GRUEN5") (pin "1") (pinfunction "QB_1") (pintype "unspecified"))
      (node (ref "R123") (pin "2") (pinfunction "2_2") (pintype "input"))
    )
    (net (code "134") (name "Net-(GRUEN5-QC)") (class "Default")
      (node (ref "GRUEN5") (pin "2") (pinfunction "QC_2") (pintype "unspecified"))
      (node (ref "R124") (pin "2") (pinfunction "2_2") (pintype "input"))
    )
    (net (code "135") (name "Net-(GRUEN5-QD)") (class "Default")
      (node (ref "GRUEN5") (pin "3") (pinfunction "QD_3") (pintype "unspecified"))
      (node (ref "R125") (pin "2") (pinfunction "2_2") (pintype "input"))
    )
    (net (code "136") (name "Net-(GRUEN5-QE)") (class "Default")
      (node (ref "GRUEN5") (pin "4") (pinfunction "QE_4") (pintype "unspecified"))
      (node (ref "R126") (pin "2") (pinfunction "2_2") (pintype "input"))
    )
    (net (code "137") (name "Net-(GRUEN5-QF)") (class "Default")
      (node (ref "GRUEN5") (pin "5") (pinfunction "QF_5") (pintype "unspecified"))
      (node (ref "R127") (pin "2") (pinfunction "2_2") (pintype "input"))
    )
    (net (code "138") (name "Net-(GRUEN5-QG)") (class "Default")
      (node (ref "GRUEN5") (pin "6") (pinfunction "QG_6") (pintype "unspecified"))
      (node (ref "R128") (pin "2") (pinfunction "2_2") (pintype "input"))
    )
    (net (code "139") (name "Net-(GRUEN5-QH)") (class "Default")
      (node (ref "GRUEN5") (pin "7") (pinfunction "QH_7") (pintype "unspecified"))
      (node (ref "R129") (pin "2") (pinfunction "2_2") (pintype "input"))
    )
    (net (code "140") (name "Net-(GRUEN5-QH{slash}2)") (class "Default")
      (node (ref "GRUEN5") (pin "9") (pinfunction "QH/2_9") (pintype "unspecified"))
      (node (ref "GRUEN6") (pin "14") (pinfunction "SER_14") (pintype "unspecified"))
    )
    (net (code "141") (name "Net-(GRUEN5-RCLK)") (class "Default")
      (node (ref "GRUEN5") (pin "12") (pinfunction "RCLK_12") (pintype "unspecified"))
      (node (ref "GRUEN6") (pin "12") (pinfunction "RCLK_12") (pintype "unspecified"))
      (node (ref "GRUEN7") (pin "12") (pinfunction "RCLK_12") (pintype "unspecified"))
      (node (ref "GRUEN8") (pin "12") (pinfunction "RCLK_12") (pintype "unspecified"))
    )
    (net (code "142") (name "Net-(GRUEN5-SRCLK)") (class "Default")
      (node (ref "GRUEN5") (pin "11") (pinfunction "SRCLK_11") (pintype "unspecified"))
      (node (ref "GRUEN6") (pin "11") (pinfunction "SRCLK_11") (pintype "unspecified"))
      (node (ref "GRUEN7") (pin "11") (pinfunction "SRCLK_11") (pintype "unspecified"))
      (node (ref "GRUEN8") (pin "11") (pinfunction "SRCLK_11") (pintype "unspecified"))
    )
    (net (code "143") (name "Net-(GRUEN6-QA)") (class "Default")
      (node (ref "GRUEN6") (pin "15") (pinfunction "QA_15") (pintype "unspecified"))
      (node (ref "R130") (pin "2") (pinfunction "2_2") (pintype "input"))
    )
    (net (code "144") (name "Net-(GRUEN6-QB)") (class "Default")
      (node (ref "GRUEN6") (pin "1") (pinfunction "QB_1") (pintype "unspecified"))
      (node (ref "R131") (pin "2") (pinfunction "2_2") (pintype "input"))
    )
    (net (code "145") (name "Net-(GRUEN6-QC)") (class "Default")
      (node (ref "GRUEN6") (pin "2") (pinfunction "QC_2") (pintype "unspecified"))
      (node (ref "R132") (pin "2") (pinfunction "2_2") (pintype "input"))
    )
    (net (code "146") (name "Net-(GRUEN6-QD)") (class "Default")
      (node (ref "GRUEN6") (pin "3") (pinfunction "QD_3") (pintype "unspecified"))
      (node (ref "R133") (pin "2") (pinfunction "2_2") (pintype "input"))
    )
    (net (code "147") (name "Net-(GRUEN6-QE)") (class "Default")
      (node (ref "GRUEN6") (pin "4") (pinfunction "QE_4") (pintype "unspecified"))
      (node (ref "R134") (pin "2") (pinfunction "2_2") (pintype "input"))
    )
    (net (code "148") (name "Net-(GRUEN6-QF)") (class "Default")
      (node (ref "GRUEN6") (pin "5") (pinfunction "QF_5") (pintype "unspecified"))
      (node (ref "R135") (pin "2") (pinfunction "2_2") (pintype "input"))
    )
    (net (code "149") (name "Net-(GRUEN6-QG)") (class "Default")
      (node (ref "GRUEN6") (pin "6") (pinfunction "QG_6") (pintype "unspecified"))
      (node (ref "R136") (pin "2") (pinfunction "2_2") (pintype "input"))
    )
    (net (code "150") (name "Net-(GRUEN6-QH)") (class "Default")
      (node (ref "GRUEN6") (pin "7") (pinfunction "QH_7") (pintype "unspecified"))
      (node (ref "R137") (pin "2") (pinfunction "2_2") (pintype "input"))
    )
    (net (code "151") (name "Net-(GRUEN6-QH{slash}2)") (class "Default")
      (node (ref "GRUEN6") (pin "9") (pinfunction "QH/2_9") (pintype "unspecified"))
      (node (ref "GRUEN7") (pin "14") (pinfunction "SER_14") (pintype "unspecified"))
    )
    (net (code "152") (name "Net-(GRUEN7-QB)") (class "Default")
      (node (ref "GRUEN7") (pin "1") (pinfunction "QB_1") (pintype "unspecified"))
      (node (ref "R139") (pin "2") (pinfunction "2_2") (pintype "input"))
    )
    (net (code "153") (name "Net-(GRUEN7-QC)") (class "Default")
      (node (ref "GRUEN7") (pin "2") (pinfunction "QC_2") (pintype "unspecified"))
      (node (ref "R140") (pin "2") (pinfunction "2_2") (pintype "input"))
    )
    (net (code "154") (name "Net-(GRUEN7-QD)") (class "Default")
      (node (ref "GRUEN7") (pin "3") (pinfunction "QD_3") (pintype "unspecified"))
      (node (ref "R141") (pin "2") (pinfunction "2_2") (pintype "input"))
    )
    (net (code "155") (name "Net-(GRUEN7-QE)") (class "Default")
      (node (ref "GRUEN7") (pin "4") (pinfunction "QE_4") (pintype "unspecified"))
      (node (ref "R142") (pin "2") (pinfunction "2_2") (pintype "input"))
    )
    (net (code "156") (name "Net-(GRUEN7-QF)") (class "Default")
      (node (ref "GRUEN7") (pin "5") (pinfunction "QF_5") (pintype "unspecified"))
      (node (ref "R143") (pin "2") (pinfunction "2_2") (pintype "input"))
    )
    (net (code "157") (name "Net-(GRUEN7-QG)") (class "Default")
      (node (ref "GRUEN7") (pin "6") (pinfunction "QG_6") (pintype "unspecified"))
      (node (ref "R144") (pin "2") (pinfunction "2_2") (pintype "input"))
    )
    (net (code "158") (name "Net-(GRUEN7-QH)") (class "Default")
      (node (ref "GRUEN7") (pin "7") (pinfunction "QH_7") (pintype "unspecified"))
      (node (ref "R145") (pin "2") (pinfunction "2_2") (pintype "input"))
    )
    (net (code "159") (name "Net-(GRUEN7-QH{slash}2)") (class "Default")
      (node (ref "GRUEN7") (pin "9") (pinfunction "QH/2_9") (pintype "unspecified"))
      (node (ref "GRUEN8") (pin "14") (pinfunction "SER_14") (pintype "unspecified"))
    )
    (net (code "160") (name "Net-(GRUEN8-QA)") (class "Default")
      (node (ref "GRUEN8") (pin "15") (pinfunction "QA_15") (pintype "unspecified"))
      (node (ref "R146") (pin "2") (pinfunction "2_2") (pintype "input"))
    )
    (net (code "161") (name "Net-(GRUEN8-QB)") (class "Default")
      (node (ref "GRUEN8") (pin "1") (pinfunction "QB_1") (pintype "unspecified"))
      (node (ref "R147") (pin "2") (pinfunction "2_2") (pintype "input"))
    )
    (net (code "162") (name "Net-(GRUEN8-QC)") (class "Default")
      (node (ref "GRUEN8") (pin "2") (pinfunction "QC_2") (pintype "unspecified"))
      (node (ref "R148") (pin "2") (pinfunction "2_2") (pintype "input"))
    )
    (net (code "163") (name "Net-(GRUEN8-QD)") (class "Default")
      (node (ref "GRUEN8") (pin "3") (pinfunction "QD_3") (pintype "unspecified"))
      (node (ref "R149") (pin "2") (pinfunction "2_2") (pintype "input"))
    )
    (net (code "164") (name "Net-(GRUEN8-QE)") (class "Default")
      (node (ref "GRUEN8") (pin "4") (pinfunction "QE_4") (pintype "unspecified"))
      (node (ref "R150") (pin "2") (pinfunction "2_2") (pintype "input"))
    )
    (net (code "165") (name "Net-(GRUEN8-QF)") (class "Default")
      (node (ref "GRUEN8") (pin "5") (pinfunction "QF_5") (pintype "unspecified"))
      (node (ref "R151") (pin "2") (pinfunction "2_2") (pintype "input"))
    )
    (net (code "166") (name "Net-(GRUEN8-QG)") (class "Default")
      (node (ref "GRUEN8") (pin "6") (pinfunction "QG_6") (pintype "unspecified"))
      (node (ref "R152") (pin "2") (pinfunction "2_2") (pintype "input"))
    )
    (net (code "167") (name "Net-(GRUEN8-QH)") (class "Default")
      (node (ref "GRUEN8") (pin "7") (pinfunction "QH_7") (pintype "unspecified"))
      (node (ref "R153") (pin "2") (pinfunction "2_2") (pintype "input"))
    )
    (net (code "168") (name "Net-(LED2-A)") (class "Default")
      (node (ref "LED2") (pin "2") (pinfunction "A_2") (pintype "unspecified"))
      (node (ref "R20") (pin "1") (pinfunction "1_1") (pintype "input"))
    )
    (net (code "169") (name "Net-(P2-Pad1)") (class "Default")
      (node (ref "P2") (pin "1") (pinfunction "1_1") (pintype "input"))
      (node (ref "R8") (pin "1") (pinfunction "1_1") (pintype "input"))
    )
    (net (code "170") (name "Net-(P2-Pad2)") (class "Default")
      (node (ref "P2") (pin "2") (pinfunction "2_2") (pintype "input"))
      (node (ref "R7") (pin "1") (pinfunction "1_1") (pintype "input"))
    )
    (net (code "171") (name "Net-(P2-Pad3)") (class "Default")
      (node (ref "P2") (pin "3") (pinfunction "3_3") (pintype "input"))
      (node (ref "R6") (pin "1") (pinfunction "1_1") (pintype "input"))
    )
    (net (code "172") (name "Net-(P2-Pad4)") (class "Default")
      (node (ref "P2") (pin "4") (pinfunction "4_4") (pintype "input"))
      (node (ref "R5") (pin "1") (pinfunction "1_1") (pintype "input"))
    )
    (net (code "173") (name "Net-(P2-Pad5)") (class "Default")
      (node (ref "P2") (pin "5") (pinfunction "5_5") (pintype "input"))
      (node (ref "R4") (pin "1") (pinfunction "1_1") (pintype "input"))
    )
    (net (code "174") (name "Net-(P2-Pad6)") (class "Default")
      (node (ref "P2") (pin "6") (pinfunction "6_6") (pintype "input"))
      (node (ref "R3") (pin "1") (pinfunction "1_1") (pintype "input"))
    )
    (net (code "175") (name "Net-(P2-Pad7)") (class "Default")
      (node (ref "P2") (pin "7") (pinfunction "7_7") (pintype "input"))
      (node (ref "R2") (pin "1") (pinfunction "1_1") (pintype "input"))
    )
    (net (code "176") (name "Net-(P2-Pad8)") (class "Default")
      (node (ref "P2") (pin "8") (pinfunction "8_8") (pintype "input"))
      (node (ref "R1") (pin "1") (pinfunction "1_1") (pintype "input"))
    )
    (net (code "177") (name "Net-(P3-Pad1)") (class "Default")
      (node (ref "P3") (pin "1") (pinfunction "1_1") (pintype "input"))
      (node (ref "R16") (pin "1") (pinfunction "1_1") (pintype "input"))
    )
    (net (code "178") (name "Net-(P3-Pad2)") (class "Default")
      (node (ref "P3") (pin "2") (pinfunction "2_2") (pintype "input"))
      (node (ref "R15") (pin "1") (pinfunction "1_1") (pintype "input"))
    )
    (net (code "179") (name "Net-(P3-Pad3)") (class "Default")
      (node (ref "P3") (pin "3") (pinfunction "3_3") (pintype "input"))
      (node (ref "R14") (pin "1") (pinfunction "1_1") (pintype "input"))
    )
    (net (code "180") (name "Net-(P3-Pad4)") (class "Default")
      (node (ref "P3") (pin "4") (pinfunction "4_4") (pintype "input"))
      (node (ref "R13") (pin "1") (pinfunction "1_1") (pintype "input"))
    )
    (net (code "181") (name "Net-(P3-Pad5)") (class "Default")
      (node (ref "P3") (pin "5") (pinfunction "5_5") (pintype "input"))
      (node (ref "R12") (pin "1") (pinfunction "1_1") (pintype "input"))
    )
    (net (code "182") (name "Net-(P3-Pad6)") (class "Default")
      (node (ref "P3") (pin "6") (pinfunction "6_6") (pintype "input"))
      (node (ref "R11") (pin "1") (pinfunction "1_1") (pintype "input"))
    )
    (net (code "183") (name "Net-(P3-Pad7)") (class "Default")
      (node (ref "P3") (pin "7") (pinfunction "7_7") (pintype "input"))
      (node (ref "R10") (pin "1") (pinfunction "1_1") (pintype "input"))
    )
    (net (code "184") (name "Net-(P3-Pad8)") (class "Default")
      (node (ref "P3") (pin "8") (pinfunction "8_8") (pintype "input"))
      (node (ref "R9") (pin "1") (pinfunction "1_1") (pintype "input"))
    )
    (net (code "185") (name "Net-(P4-Pad1)") (class "Default")
      (node (ref "P4") (pin "1") (pinfunction "1_1") (pintype "input"))
      (node (ref "R25") (pin "1") (pinfunction "1_1") (pintype "input"))
    )
    (net (code "186") (name "Net-(P4-Pad2)") (class "Default")
      (node (ref "P4") (pin "2") (pinfunction "2_2") (pintype "input"))
      (node (ref "R24") (pin "1") (pinfunction "1_1") (pintype "input"))
    )
    (net (code "187") (name "Net-(P4-Pad3)") (class "Default")
      (node (ref "P4") (pin "3") (pinfunction "3_3") (pintype "input"))
      (node (ref "R23") (pin "1") (pinfunction "1_1") (pintype "input"))
    )
    (net (code "188") (name "Net-(P4-Pad4)") (class "Default")
      (node (ref "P4") (pin "4") (pinfunction "4_4") (pintype "input"))
      (node (ref "R22") (pin "1") (pinfunction "1_1") (pintype "input"))
    )
    (net (code "189") (name "Net-(P4-Pad5)") (class "Default")
      (node (ref "P4") (pin "5") (pinfunction "5_5") (pintype "input"))
      (node (ref "R21") (pin "1") (pinfunction "1_1") (pintype "input"))
    )
    (net (code "190") (name "Net-(P4-Pad6)") (class "Default")
      (node (ref "P4") (pin "6") (pinfunction "6_6") (pintype "input"))
      (node (ref "R19") (pin "1") (pinfunction "1_1") (pintype "input"))
    )
    (net (code "191") (name "Net-(P4-Pad7)") (class "Default")
      (node (ref "P4") (pin "7") (pinfunction "7_7") (pintype "input"))
      (node (ref "R18") (pin "1") (pinfunction "1_1") (pintype "input"))
    )
    (net (code "192") (name "Net-(P4-Pad8)") (class "Default")
      (node (ref "P4") (pin "8") (pinfunction "8_8") (pintype "input"))
      (node (ref "R17") (pin "1") (pinfunction "1_1") (pintype "input"))
    )
    (net (code "193") (name "Net-(P5-Pad1)") (class "Default")
      (node (ref "P5") (pin "1") (pinfunction "1_1") (pintype "input"))
      (node (ref "R33") (pin "1") (pinfunction "1_1") (pintype "input"))
    )
    (net (code "194") (name "Net-(P5-Pad2)") (class "Default")
      (node (ref "P5") (pin "2") (pinfunction "2_2") (pintype "input"))
      (node (ref "R32") (pin "1") (pinfunction "1_1") (pintype "input"))
    )
    (net (code "195") (name "Net-(P5-Pad3)") (class "Default")
      (node (ref "P5") (pin "3") (pinfunction "3_3") (pintype "input"))
      (node (ref "R31") (pin "1") (pinfunction "1_1") (pintype "input"))
    )
    (net (code "196") (name "Net-(P5-Pad4)") (class "Default")
      (node (ref "P5") (pin "4") (pinfunction "4_4") (pintype "input"))
      (node (ref "R30") (pin "1") (pinfunction "1_1") (pintype "input"))
    )
    (net (code "197") (name "Net-(P5-Pad5)") (class "Default")
      (node (ref "P5") (pin "5") (pinfunction "5_5") (pintype "input"))
      (node (ref "R29") (pin "1") (pinfunction "1_1") (pintype "input"))
    )
    (net (code "198") (name "Net-(P5-Pad6)") (class "Default")
      (node (ref "P5") (pin "6") (pinfunction "6_6") (pintype "input"))
      (node (ref "R28") (pin "1") (pinfunction "1_1") (pintype "input"))
    )
    (net (code "199") (name "Net-(P5-Pad7)") (class "Default")
      (node (ref "P5") (pin "7") (pinfunction "7_7") (pintype "input"))
      (node (ref "R27") (pin "1") (pinfunction "1_1") (pintype "input"))
    )
    (net (code "200") (name "Net-(P5-Pad8)") (class "Default")
      (node (ref "P5") (pin "8") (pinfunction "8_8") (pintype "input"))
      (node (ref "R26") (pin "1") (pinfunction "1_1") (pintype "input"))
    )
    (net (code "201") (name "Net-(P6-Pad1)") (class "Default")
      (node (ref "P6") (pin "1") (pinfunction "1_1") (pintype "input"))
      (node (ref "R41") (pin "1") (pinfunction "1_1") (pintype "input"))
    )
    (net (code "202") (name "Net-(P6-Pad2)") (class "Default")
      (node (ref "P6") (pin "2") (pinfunction "2_2") (pintype "input"))
      (node (ref "R40") (pin "1") (pinfunction "1_1") (pintype "input"))
    )
    (net (code "203") (name "Net-(P6-Pad3)") (class "Default")
      (node (ref "P6") (pin "3") (pinfunction "3_3") (pintype "input"))
      (node (ref "R39") (pin "1") (pinfunction "1_1") (pintype "input"))
    )
    (net (code "204") (name "Net-(P6-Pad4)") (class "Default")
      (node (ref "P6") (pin "4") (pinfunction "4_4") (pintype "input"))
      (node (ref "R38") (pin "1") (pinfunction "1_1") (pintype "input"))
    )
    (net (code "205") (name "Net-(P6-Pad5)") (class "Default")
      (node (ref "P6") (pin "5") (pinfunction "5_5") (pintype "input"))
      (node (ref "R37") (pin "1") (pinfunction "1_1") (pintype "input"))
    )
    (net (code "206") (name "Net-(P6-Pad6)") (class "Default")
      (node (ref "P6") (pin "6") (pinfunction "6_6") (pintype "input"))
      (node (ref "R36") (pin "1") (pinfunction "1_1") (pintype "input"))
    )
    (net (code "207") (name "Net-(P6-Pad7)") (class "Default")
      (node (ref "P6") (pin "7") (pinfunction "7_7") (pintype "input"))
      (node (ref "R35") (pin "1") (pinfunction "1_1") (pintype "input"))
    )
    (net (code "208") (name "Net-(P6-Pad8)") (class "Default")
      (node (ref "P6") (pin "8") (pinfunction "8_8") (pintype "input"))
      (node (ref "R34") (pin "1") (pinfunction "1_1") (pintype "input"))
    )
    (net (code "209") (name "Net-(P7-Pad1)") (class "Default")
      (node (ref "P7") (pin "1") (pinfunction "1_1") (pintype "input"))
      (node (ref "R49") (pin "1") (pinfunction "1_1") (pintype "input"))
    )
    (net (code "210") (name "Net-(P7-Pad2)") (class "Default")
      (node (ref "P7") (pin "2") (pinfunction "2_2") (pintype "input"))
      (node (ref "R48") (pin "1") (pinfunction "1_1") (pintype "input"))
    )
    (net (code "211") (name "Net-(P7-Pad3)") (class "Default")
      (node (ref "P7") (pin "3") (pinfunction "3_3") (pintype "input"))
      (node (ref "R47") (pin "1") (pinfunction "1_1") (pintype "input"))
    )
    (net (code "212") (name "Net-(P7-Pad4)") (class "Default")
      (node (ref "P7") (pin "4") (pinfunction "4_4") (pintype "input"))
      (node (ref "R46") (pin "1") (pinfunction "1_1") (pintype "input"))
    )
    (net (code "213") (name "Net-(P7-Pad5)") (class "Default")
      (node (ref "P7") (pin "5") (pinfunction "5_5") (pintype "input"))
      (node (ref "R45") (pin "1") (pinfunction "1_1") (pintype "input"))
    )
    (net (code "214") (name "Net-(P7-Pad6)") (class "Default")
      (node (ref "P7") (pin "6") (pinfunction "6_6") (pintype "input"))
      (node (ref "R44") (pin "1") (pinfunction "1_1") (pintype "input"))
    )
    (net (code "215") (name "Net-(P7-Pad7)") (class "Default")
      (node (ref "P7") (pin "7") (pinfunction "7_7") (pintype "input"))
      (node (ref "R43") (pin "1") (pinfunction "1_1") (pintype "input"))
    )
    (net (code "216") (name "Net-(P7-Pad8)") (class "Default")
      (node (ref "P7") (pin "8") (pinfunction "8_8") (pintype "input"))
      (node (ref "R42") (pin "1") (pinfunction "1_1") (pintype "input"))
    )
    (net (code "217") (name "Net-(P8-Pad1)") (class "Default")
      (node (ref "P8") (pin "1") (pinfunction "1_1") (pintype "input"))
      (node (ref "R57") (pin "1") (pinfunction "1_1") (pintype "input"))
    )
    (net (code "218") (name "Net-(P8-Pad2)") (class "Default")
      (node (ref "P8") (pin "2") (pinfunction "2_2") (pintype "input"))
      (node (ref "R56") (pin "1") (pinfunction "1_1") (pintype "input"))
    )
    (net (code "219") (name "Net-(P8-Pad3)") (class "Default")
      (node (ref "P8") (pin "3") (pinfunction "3_3") (pintype "input"))
      (node (ref "R55") (pin "1") (pinfunction "1_1") (pintype "input"))
    )
    (net (code "220") (name "Net-(P8-Pad4)") (class "Default")
      (node (ref "P8") (pin "4") (pinfunction "4_4") (pintype "input"))
      (node (ref "R54") (pin "1") (pinfunction "1_1") (pintype "input"))
    )
    (net (code "221") (name "Net-(P8-Pad5)") (class "Default")
      (node (ref "P8") (pin "5") (pinfunction "5_5") (pintype "input"))
      (node (ref "R53") (pin "1") (pinfunction "1_1") (pintype "input"))
    )
    (net (code "222") (name "Net-(P8-Pad6)") (class "Default")
      (node (ref "P8") (pin "6") (pinfunction "6_6") (pintype "input"))
      (node (ref "R52") (pin "1") (pinfunction "1_1") (pintype "input"))
    )
    (net (code "223") (name "Net-(P8-Pad7)") (class "Default")
      (node (ref "P8") (pin "7") (pinfunction "7_7") (pintype "input"))
      (node (ref "R51") (pin "1") (pinfunction "1_1") (pintype "input"))
    )
    (net (code "224") (name "Net-(P8-Pad8)") (class "Default")
      (node (ref "P8") (pin "8") (pinfunction "8_8") (pintype "input"))
      (node (ref "R50") (pin "1") (pinfunction "1_1") (pintype "input"))
    )
    (net (code "225") (name "Net-(P9-Pad1)") (class "Default")
      (node (ref "P9") (pin "1") (pinfunction "1_1") (pintype "input"))
      (node (ref "R65") (pin "1") (pinfunction "1_1") (pintype "input"))
    )
    (net (code "226") (name "Net-(P9-Pad2)") (class "Default")
      (node (ref "P9") (pin "2") (pinfunction "2_2") (pintype "input"))
      (node (ref "R64") (pin "1") (pinfunction "1_1") (pintype "input"))
    )
    (net (code "227") (name "Net-(P9-Pad3)") (class "Default")
      (node (ref "P9") (pin "3") (pinfunction "3_3") (pintype "input"))
      (node (ref "R63") (pin "1") (pinfunction "1_1") (pintype "input"))
    )
    (net (code "228") (name "Net-(P9-Pad4)") (class "Default")
      (node (ref "P9") (pin "4") (pinfunction "4_4") (pintype "input"))
      (node (ref "R62") (pin "1") (pinfunction "1_1") (pintype "input"))
    )
    (net (code "229") (name "Net-(P9-Pad5)") (class "Default")
      (node (ref "P9") (pin "5") (pinfunction "5_5") (pintype "input"))
      (node (ref "R61") (pin "1") (pinfunction "1_1") (pintype "input"))
    )
    (net (code "230") (name "Net-(P9-Pad6)") (class "Default")
      (node (ref "P9") (pin "6") (pinfunction "6_6") (pintype "input"))
      (node (ref "R60") (pin "1") (pinfunction "1_1") (pintype "input"))
    )
    (net (code "231") (name "Net-(P9-Pad7)") (class "Default")
      (node (ref "P9") (pin "7") (pinfunction "7_7") (pintype "input"))
      (node (ref "R59") (pin "1") (pinfunction "1_1") (pintype "input"))
    )
    (net (code "232") (name "Net-(P9-Pad8)") (class "Default")
      (node (ref "P9") (pin "8") (pinfunction "8_8") (pintype "input"))
      (node (ref "R58") (pin "1") (pinfunction "1_1") (pintype "input"))
    )
    (net (code "233") (name "Net-(P10-Pad1)") (class "Default")
      (node (ref "P10") (pin "1") (pinfunction "1_1") (pintype "input"))
      (node (ref "R73") (pin "1") (pinfunction "1_1") (pintype "input"))
    )
    (net (code "234") (name "Net-(P10-Pad2)") (class "Default")
      (node (ref "P10") (pin "2") (pinfunction "2_2") (pintype "input"))
      (node (ref "R72") (pin "1") (pinfunction "1_1") (pintype "input"))
    )
    (net (code "235") (name "Net-(P10-Pad3)") (class "Default")
      (node (ref "P10") (pin "3") (pinfunction "3_3") (pintype "input"))
      (node (ref "R71") (pin "1") (pinfunction "1_1") (pintype "input"))
    )
    (net (code "236") (name "Net-(P10-Pad4)") (class "Default")
      (node (ref "P10") (pin "4") (pinfunction "4_4") (pintype "input"))
      (node (ref "R70") (pin "1") (pinfunction "1_1") (pintype "input"))
    )
    (net (code "237") (name "Net-(P10-Pad5)") (class "Default")
      (node (ref "P10") (pin "5") (pinfunction "5_5") (pintype "input"))
      (node (ref "R69") (pin "1") (pinfunction "1_1") (pintype "input"))
    )
    (net (code "238") (name "Net-(P10-Pad6)") (class "Default")
      (node (ref "P10") (pin "6") (pinfunction "6_6") (pintype "input"))
      (node (ref "R68") (pin "1") (pinfunction "1_1") (pintype "input"))
    )
    (net (code "239") (name "Net-(P10-Pad7)") (class "Default")
      (node (ref "P10") (pin "7") (pinfunction "7_7") (pintype "input"))
      (node (ref "R67") (pin "1") (pinfunction "1_1") (pintype "input"))
    )
    (net (code "240") (name "Net-(P10-Pad8)") (class "Default")
      (node (ref "P10") (pin "8") (pinfunction "8_8") (pintype "input"))
      (node (ref "R66") (pin "1") (pinfunction "1_1") (pintype "input"))
    )
    (net (code "241") (name "Net-(P11-Pad1)") (class "Default")
      (node (ref "P11") (pin "1") (pinfunction "1_1") (pintype "input"))
      (node (ref "R81") (pin "1") (pinfunction "1_1") (pintype "input"))
    )
    (net (code "242") (name "Net-(P11-Pad2)") (class "Default")
      (node (ref "P11") (pin "2") (pinfunction "2_2") (pintype "input"))
      (node (ref "R80") (pin "1") (pinfunction "1_1") (pintype "input"))
    )
    (net (code "243") (name "Net-(P11-Pad3)") (class "Default")
      (node (ref "P11") (pin "3") (pinfunction "3_3") (pintype "input"))
      (node (ref "R79") (pin "1") (pinfunction "1_1") (pintype "input"))
    )
    (net (code "244") (name "Net-(P11-Pad4)") (class "Default")
      (node (ref "P11") (pin "4") (pinfunction "4_4") (pintype "input"))
      (node (ref "R78") (pin "1") (pinfunction "1_1") (pintype "input"))
    )
    (net (code "245") (name "Net-(P11-Pad5)") (class "Default")
      (node (ref "P11") (pin "5") (pinfunction "5_5") (pintype "input"))
      (node (ref "R77") (pin "1") (pinfunction "1_1") (pintype "input"))
    )
    (net (code "246") (name "Net-(P11-Pad6)") (class "Default")
      (node (ref "P11") (pin "6") (pinfunction "6_6") (pintype "input"))
      (node (ref "R76") (pin "1") (pinfunction "1_1") (pintype "input"))
    )
    (net (code "247") (name "Net-(P11-Pad7)") (class "Default")
      (node (ref "P11") (pin "7") (pinfunction "7_7") (pintype "input"))
      (node (ref "R75") (pin "1") (pinfunction "1_1") (pintype "input"))
    )
    (net (code "248") (name "Net-(P11-Pad8)") (class "Default")
      (node (ref "P11") (pin "8") (pinfunction "8_8") (pintype "input"))
      (node (ref "R74") (pin "1") (pinfunction "1_1") (pintype "input"))
    )
    (net (code "249") (name "Net-(P13-Pad1)") (class "Default")
      (node (ref "P13") (pin "1") (pinfunction "1_1") (pintype "input"))
      (node (ref "R89") (pin "1") (pinfunction "1_1") (pintype "input"))
    )
    (net (code "250") (name "Net-(P13-Pad2)") (class "Default")
      (node (ref "P13") (pin "2") (pinfunction "2_2") (pintype "input"))
      (node (ref "R88") (pin "1") (pinfunction "1_1") (pintype "input"))
    )
    (net (code "251") (name "Net-(P13-Pad3)") (class "Default")
      (node (ref "P13") (pin "3") (pinfunction "3_3") (pintype "input"))
      (node (ref "R87") (pin "1") (pinfunction "1_1") (pintype "input"))
    )
    (net (code "252") (name "Net-(P13-Pad4)") (class "Default")
      (node (ref "P13") (pin "4") (pinfunction "4_4") (pintype "input"))
      (node (ref "R86") (pin "1") (pinfunction "1_1") (pintype "input"))
    )
    (net (code "253") (name "Net-(P13-Pad5)") (class "Default")
      (node (ref "P13") (pin "5") (pinfunction "5_5") (pintype "input"))
      (node (ref "R85") (pin "1") (pinfunction "1_1") (pintype "input"))
    )
    (net (code "254") (name "Net-(P13-Pad6)") (class "Default")
      (node (ref "P13") (pin "6") (pinfunction "6_6") (pintype "input"))
      (node (ref "R84") (pin "1") (pinfunction "1_1") (pintype "input"))
    )
    (net (code "255") (name "Net-(P13-Pad7)") (class "Default")
      (node (ref "P13") (pin "7") (pinfunction "7_7") (pintype "input"))
      (node (ref "R83") (pin "1") (pinfunction "1_1") (pintype "input"))
    )
    (net (code "256") (name "Net-(P13-Pad8)") (class "Default")
      (node (ref "P13") (pin "8") (pinfunction "8_8") (pintype "input"))
      (node (ref "R82") (pin "1") (pinfunction "1_1") (pintype "input"))
    )
    (net (code "257") (name "Net-(P14-Pad1)") (class "Default")
      (node (ref "P14") (pin "1") (pinfunction "1_1") (pintype "input"))
      (node (ref "R97") (pin "1") (pinfunction "1_1") (pintype "input"))
    )
    (net (code "258") (name "Net-(P14-Pad2)") (class "Default")
      (node (ref "P14") (pin "2") (pinfunction "2_2") (pintype "input"))
      (node (ref "R96") (pin "1") (pinfunction "1_1") (pintype "input"))
    )
    (net (code "259") (name "Net-(P14-Pad3)") (class "Default")
      (node (ref "P14") (pin "3") (pinfunction "3_3") (pintype "input"))
      (node (ref "R95") (pin "1") (pinfunction "1_1") (pintype "input"))
    )
    (net (code "260") (name "Net-(P14-Pad4)") (class "Default")
      (node (ref "P14") (pin "4") (pinfunction "4_4") (pintype "input"))
      (node (ref "R94") (pin "1") (pinfunction "1_1") (pintype "input"))
    )
    (net (code "261") (name "Net-(P14-Pad5)") (class "Default")
      (node (ref "P14") (pin "5") (pinfunction "5_5") (pintype "input"))
      (node (ref "R93") (pin "1") (pinfunction "1_1") (pintype "input"))
    )
    (net (code "262") (name "Net-(P14-Pad6)") (class "Default")
      (node (ref "P14") (pin "6") (pinfunction "6_6") (pintype "input"))
      (node (ref "R92") (pin "1") (pinfunction "1_1") (pintype "input"))
    )
    (net (code "263") (name "Net-(P14-Pad7)") (class "Default")
      (node (ref "P14") (pin "7") (pinfunction "7_7") (pintype "input"))
      (node (ref "R91") (pin "1") (pinfunction "1_1") (pintype "input"))
    )
    (net (code "264") (name "Net-(P14-Pad8)") (class "Default")
      (node (ref "P14") (pin "8") (pinfunction "8_8") (pintype "input"))
      (node (ref "R90") (pin "1") (pinfunction "1_1") (pintype "input"))
    )
    (net (code "265") (name "Net-(P15-Pad1)") (class "Default")
      (node (ref "P15") (pin "1") (pinfunction "1_1") (pintype "input"))
      (node (ref "R105") (pin "1") (pinfunction "1_1") (pintype "input"))
    )
    (net (code "266") (name "Net-(P15-Pad2)") (class "Default")
      (node (ref "P15") (pin "2") (pinfunction "2_2") (pintype "input"))
      (node (ref "R104") (pin "1") (pinfunction "1_1") (pintype "input"))
    )
    (net (code "267") (name "Net-(P15-Pad3)") (class "Default")
      (node (ref "P15") (pin "3") (pinfunction "3_3") (pintype "input"))
      (node (ref "R103") (pin "1") (pinfunction "1_1") (pintype "input"))
    )
    (net (code "268") (name "Net-(P15-Pad4)") (class "Default")
      (node (ref "P15") (pin "4") (pinfunction "4_4") (pintype "input"))
      (node (ref "R102") (pin "1") (pinfunction "1_1") (pintype "input"))
    )
    (net (code "269") (name "Net-(P15-Pad5)") (class "Default")
      (node (ref "P15") (pin "5") (pinfunction "5_5") (pintype "input"))
      (node (ref "R101") (pin "1") (pinfunction "1_1") (pintype "input"))
    )
    (net (code "270") (name "Net-(P15-Pad6)") (class "Default")
      (node (ref "P15") (pin "6") (pinfunction "6_6") (pintype "input"))
      (node (ref "R100") (pin "1") (pinfunction "1_1") (pintype "input"))
    )
    (net (code "271") (name "Net-(P15-Pad7)") (class "Default")
      (node (ref "P15") (pin "7") (pinfunction "7_7") (pintype "input"))
      (node (ref "R99") (pin "1") (pinfunction "1_1") (pintype "input"))
    )
    (net (code "272") (name "Net-(P15-Pad8)") (class "Default")
      (node (ref "P15") (pin "8") (pinfunction "8_8") (pintype "input"))
      (node (ref "R98") (pin "1") (pinfunction "1_1") (pintype "input"))
    )
    (net (code "273") (name "Net-(P16-Pad1)") (class "Default")
      (node (ref "P16") (pin "1") (pinfunction "1_1") (pintype "input"))
      (node (ref "R113") (pin "1") (pinfunction "1_1") (pintype "input"))
    )
    (net (code "274") (name "Net-(P16-Pad2)") (class "Default")
      (node (ref "P16") (pin "2") (pinfunction "2_2") (pintype "input"))
      (node (ref "R112") (pin "1") (pinfunction "1_1") (pintype "input"))
    )
    (net (code "275") (name "Net-(P16-Pad3)") (class "Default")
      (node (ref "P16") (pin "3") (pinfunction "3_3") (pintype "input"))
      (node (ref "R111") (pin "1") (pinfunction "1_1") (pintype "input"))
    )
    (net (code "276") (name "Net-(P16-Pad4)") (class "Default")
      (node (ref "P16") (pin "4") (pinfunction "4_4") (pintype "input"))
      (node (ref "R110") (pin "1") (pinfunction "1_1") (pintype "input"))
    )
    (net (code "277") (name "Net-(P16-Pad5)") (class "Default")
      (node (ref "P16") (pin "5") (pinfunction "5_5") (pintype "input"))
      (node (ref "R109") (pin "1") (pinfunction "1_1") (pintype "input"))
    )
    (net (code "278") (name "Net-(P16-Pad6)") (class "Default")
      (node (ref "P16") (pin "6") (pinfunction "6_6") (pintype "input"))
      (node (ref "R108") (pin "1") (pinfunction "1_1") (pintype "input"))
    )
    (net (code "279") (name "Net-(P16-Pad7)") (class "Default")
      (node (ref "P16") (pin "7") (pinfunction "7_7") (pintype "input"))
      (node (ref "R107") (pin "1") (pinfunction "1_1") (pintype "input"))
    )
    (net (code "280") (name "Net-(P16-Pad8)") (class "Default")
      (node (ref "P16") (pin "8") (pinfunction "8_8") (pintype "input"))
      (node (ref "R106") (pin "1") (pinfunction "1_1") (pintype "input"))
    )
    (net (code "281") (name "Net-(P17-Pad1)") (class "Default")
      (node (ref "P17") (pin "1") (pinfunction "1_1") (pintype "input"))
      (node (ref "R121") (pin "1") (pinfunction "1_1") (pintype "input"))
    )
    (net (code "282") (name "Net-(P17-Pad2)") (class "Default")
      (node (ref "P17") (pin "2") (pinfunction "2_2") (pintype "input"))
      (node (ref "R120") (pin "1") (pinfunction "1_1") (pintype "input"))
    )
    (net (code "283") (name "Net-(P17-Pad3)") (class "Default")
      (node (ref "P17") (pin "3") (pinfunction "3_3") (pintype "input"))
      (node (ref "R119") (pin "1") (pinfunction "1_1") (pintype "input"))
    )
    (net (code "284") (name "Net-(P17-Pad4)") (class "Default")
      (node (ref "P17") (pin "4") (pinfunction "4_4") (pintype "input"))
      (node (ref "R118") (pin "1") (pinfunction "1_1") (pintype "input"))
    )
    (net (code "285") (name "Net-(P17-Pad5)") (class "Default")
      (node (ref "P17") (pin "5") (pinfunction "5_5") (pintype "input"))
      (node (ref "R117") (pin "1") (pinfunction "1_1") (pintype "input"))
    )
    (net (code "286") (name "Net-(P17-Pad6)") (class "Default")
      (node (ref "P17") (pin "6") (pinfunction "6_6") (pintype "input"))
      (node (ref "R116") (pin "1") (pinfunction "1_1") (pintype "input"))
    )
    (net (code "287") (name "Net-(P17-Pad7)") (class "Default")
      (node (ref "P17") (pin "7") (pinfunction "7_7") (pintype "input"))
      (node (ref "R115") (pin "1") (pinfunction "1_1") (pintype "input"))
    )
    (net (code "288") (name "Net-(P17-Pad8)") (class "Default")
      (node (ref "P17") (pin "8") (pinfunction "8_8") (pintype "input"))
      (node (ref "R114") (pin "1") (pinfunction "1_1") (pintype "input"))
    )
    (net (code "289") (name "Net-(P18-Pad1)") (class "Default")
      (node (ref "P18") (pin "1") (pinfunction "1_1") (pintype "input"))
      (node (ref "R129") (pin "1") (pinfunction "1_1") (pintype "input"))
    )
    (net (code "290") (name "Net-(P18-Pad2)") (class "Default")
      (node (ref "P18") (pin "2") (pinfunction "2_2") (pintype "input"))
      (node (ref "R128") (pin "1") (pinfunction "1_1") (pintype "input"))
    )
    (net (code "291") (name "Net-(P18-Pad3)") (class "Default")
      (node (ref "P18") (pin "3") (pinfunction "3_3") (pintype "input"))
      (node (ref "R127") (pin "1") (pinfunction "1_1") (pintype "input"))
    )
    (net (code "292") (name "Net-(P18-Pad4)") (class "Default")
      (node (ref "P18") (pin "4") (pinfunction "4_4") (pintype "input"))
      (node (ref "R126") (pin "1") (pinfunction "1_1") (pintype "input"))
    )
    (net (code "293") (name "Net-(P18-Pad5)") (class "Default")
      (node (ref "P18") (pin "5") (pinfunction "5_5") (pintype "input"))
      (node (ref "R125") (pin "1") (pinfunction "1_1") (pintype "input"))
    )
    (net (code "294") (name "Net-(P18-Pad6)") (class "Default")
      (node (ref "P18") (pin "6") (pinfunction "6_6") (pintype "input"))
      (node (ref "R124") (pin "1") (pinfunction "1_1") (pintype "input"))
    )
    (net (code "295") (name "Net-(P18-Pad7)") (class "Default")
      (node (ref "P18") (pin "7") (pinfunction "7_7") (pintype "input"))
      (node (ref "R123") (pin "1") (pinfunction "1_1") (pintype "input"))
    )
    (net (code "296") (name "Net-(P18-Pad8)") (class "Default")
      (node (ref "P18") (pin "8") (pinfunction "8_8") (pintype "input"))
      (node (ref "R122") (pin "1") (pinfunction "1_1") (pintype "input"))
    )
    (net (code "297") (name "Net-(P19-Pad1)") (class "Default")
      (node (ref "P19") (pin "1") (pinfunction "1_1") (pintype "input"))
      (node (ref "R137") (pin "1") (pinfunction "1_1") (pintype "input"))
    )
    (net (code "298") (name "Net-(P19-Pad2)") (class "Default")
      (node (ref "P19") (pin "2") (pinfunction "2_2") (pintype "input"))
      (node (ref "R136") (pin "1") (pinfunction "1_1") (pintype "input"))
    )
    (net (code "299") (name "Net-(P19-Pad3)") (class "Default")
      (node (ref "P19") (pin "3") (pinfunction "3_3") (pintype "input"))
      (node (ref "R135") (pin "1") (pinfunction "1_1") (pintype "input"))
    )
    (net (code "300") (name "Net-(P19-Pad4)") (class "Default")
      (node (ref "P19") (pin "4") (pinfunction "4_4") (pintype "input"))
      (node (ref "R134") (pin "1") (pinfunction "1_1") (pintype "input"))
    )
    (net (code "301") (name "Net-(P19-Pad5)") (class "Default")
      (node (ref "P19") (pin "5") (pinfunction "5_5") (pintype "input"))
      (node (ref "R133") (pin "1") (pinfunction "1_1") (pintype "input"))
    )
    (net (code "302") (name "Net-(P19-Pad6)") (class "Default")
      (node (ref "P19") (pin "6") (pinfunction "6_6") (pintype "input"))
      (node (ref "R132") (pin "1") (pinfunction "1_1") (pintype "input"))
    )
    (net (code "303") (name "Net-(P19-Pad7)") (class "Default")
      (node (ref "P19") (pin "7") (pinfunction "7_7") (pintype "input"))
      (node (ref "R131") (pin "1") (pinfunction "1_1") (pintype "input"))
    )
    (net (code "304") (name "Net-(P19-Pad8)") (class "Default")
      (node (ref "P19") (pin "8") (pinfunction "8_8") (pintype "input"))
      (node (ref "R130") (pin "1") (pinfunction "1_1") (pintype "input"))
    )
    (net (code "305") (name "Net-(P20-Pad1)") (class "Default")
      (node (ref "P20") (pin "1") (pinfunction "1_1") (pintype "input"))
      (node (ref "R145") (pin "1") (pinfunction "1_1") (pintype "input"))
    )
    (net (code "306") (name "Net-(P20-Pad2)") (class "Default")
      (node (ref "P20") (pin "2") (pinfunction "2_2") (pintype "input"))
      (node (ref "R144") (pin "1") (pinfunction "1_1") (pintype "input"))
    )
    (net (code "307") (name "Net-(P20-Pad3)") (class "Default")
      (node (ref "P20") (pin "3") (pinfunction "3_3") (pintype "input"))
      (node (ref "R143") (pin "1") (pinfunction "1_1") (pintype "input"))
    )
    (net (code "308") (name "Net-(P20-Pad4)") (class "Default")
      (node (ref "P20") (pin "4") (pinfunction "4_4") (pintype "input"))
      (node (ref "R142") (pin "1") (pinfunction "1_1") (pintype "input"))
    )
    (net (code "309") (name "Net-(P20-Pad5)") (class "Default")
      (node (ref "P20") (pin "5") (pinfunction "5_5") (pintype "input"))
      (node (ref "R141") (pin "1") (pinfunction "1_1") (pintype "input"))
    )
    (net (code "310") (name "Net-(P20-Pad6)") (class "Default")
      (node (ref "P20") (pin "6") (pinfunction "6_6") (pintype "input"))
      (node (ref "R140") (pin "1") (pinfunction "1_1") (pintype "input"))
    )
    (net (code "311") (name "Net-(P20-Pad7)") (class "Default")
      (node (ref "P20") (pin "7") (pinfunction "7_7") (pintype "input"))
      (node (ref "R139") (pin "1") (pinfunction "1_1") (pintype "input"))
    )
    (net (code "312") (name "Net-(P20-Pad8)") (class "Default")
      (node (ref "P20") (pin "8") (pinfunction "8_8") (pintype "input"))
      (node (ref "R138") (pin "1") (pinfunction "1_1") (pintype "input"))
    )
    (net (code "313") (name "Net-(P21-Pad1)") (class "Default")
      (node (ref "P21") (pin "1") (pinfunction "1_1") (pintype "input"))
      (node (ref "R153") (pin "1") (pinfunction "1_1") (pintype "input"))
    )
    (net (code "314") (name "Net-(P21-Pad2)") (class "Default")
      (node (ref "P21") (pin "2") (pinfunction "2_2") (pintype "input"))
      (node (ref "R152") (pin "1") (pinfunction "1_1") (pintype "input"))
    )
    (net (code "315") (name "Net-(P21-Pad3)") (class "Default")
      (node (ref "P21") (pin "3") (pinfunction "3_3") (pintype "input"))
      (node (ref "R151") (pin "1") (pinfunction "1_1") (pintype "input"))
    )
    (net (code "316") (name "Net-(P21-Pad4)") (class "Default")
      (node (ref "P21") (pin "4") (pinfunction "4_4") (pintype "input"))
      (node (ref "R150") (pin "1") (pinfunction "1_1") (pintype "input"))
    )
    (net (code "317") (name "Net-(P21-Pad5)") (class "Default")
      (node (ref "P21") (pin "5") (pinfunction "5_5") (pintype "input"))
      (node (ref "R149") (pin "1") (pinfunction "1_1") (pintype "input"))
    )
    (net (code "318") (name "Net-(P21-Pad6)") (class "Default")
      (node (ref "P21") (pin "6") (pinfunction "6_6") (pintype "input"))
      (node (ref "R148") (pin "1") (pinfunction "1_1") (pintype "input"))
    )
    (net (code "319") (name "Net-(P21-Pad7)") (class "Default")
      (node (ref "P21") (pin "7") (pinfunction "7_7") (pintype "input"))
      (node (ref "R147") (pin "1") (pinfunction "1_1") (pintype "input"))
    )
    (net (code "320") (name "Net-(P21-Pad8)") (class "Default")
      (node (ref "P21") (pin "8") (pinfunction "8_8") (pintype "input"))
      (node (ref "R146") (pin "1") (pinfunction "1_1") (pintype "input"))
    )
    (net (code "321") (name "Net-(P22-Pad1)") (class "Default")
      (node (ref "P22") (pin "1") (pinfunction "1_1") (pintype "input"))
      (node (ref "R161") (pin "1") (pinfunction "1_1") (pintype "input"))
    )
    (net (code "322") (name "Net-(P22-Pad2)") (class "Default")
      (node (ref "P22") (pin "2") (pinfunction "2_2") (pintype "input"))
      (node (ref "R160") (pin "1") (pinfunction "1_1") (pintype "input"))
    )
    (net (code "323") (name "Net-(P22-Pad3)") (class "Default")
      (node (ref "P22") (pin "3") (pinfunction "3_3") (pintype "input"))
      (node (ref "R159") (pin "1") (pinfunction "1_1") (pintype "input"))
    )
    (net (code "324") (name "Net-(P22-Pad4)") (class "Default")
      (node (ref "P22") (pin "4") (pinfunction "4_4") (pintype "input"))
      (node (ref "R158") (pin "1") (pinfunction "1_1") (pintype "input"))
    )
    (net (code "325") (name "Net-(P22-Pad5)") (class "Default")
      (node (ref "P22") (pin "5") (pinfunction "5_5") (pintype "input"))
      (node (ref "R157") (pin "1") (pinfunction "1_1") (pintype "input"))
    )
    (net (code "326") (name "Net-(P22-Pad6)") (class "Default")
      (node (ref "P22") (pin "6") (pinfunction "6_6") (pintype "input"))
      (node (ref "R156") (pin "1") (pinfunction "1_1") (pintype "input"))
    )
    (net (code "327") (name "Net-(P22-Pad7)") (class "Default")
      (node (ref "P22") (pin "7") (pinfunction "7_7") (pintype "input"))
      (node (ref "R155") (pin "1") (pinfunction "1_1") (pintype "input"))
    )
    (net (code "328") (name "Net-(P22-Pad8)") (class "Default")
      (node (ref "P22") (pin "8") (pinfunction "8_8") (pintype "input"))
      (node (ref "R154") (pin "1") (pinfunction "1_1") (pintype "input"))
    )
    (net (code "329") (name "Net-(P23-Pad1)") (class "Default")
      (node (ref "P23") (pin "1") (pinfunction "1_1") (pintype "input"))
      (node (ref "R169") (pin "1") (pinfunction "1_1") (pintype "input"))
    )
    (net (code "330") (name "Net-(P23-Pad2)") (class "Default")
      (node (ref "P23") (pin "2") (pinfunction "2_2") (pintype "input"))
      (node (ref "R168") (pin "1") (pinfunction "1_1") (pintype "input"))
    )
    (net (code "331") (name "Net-(P23-Pad3)") (class "Default")
      (node (ref "P23") (pin "3") (pinfunction "3_3") (pintype "input"))
      (node (ref "R167") (pin "1") (pinfunction "1_1") (pintype "input"))
    )
    (net (code "332") (name "Net-(P23-Pad4)") (class "Default")
      (node (ref "P23") (pin "4") (pinfunction "4_4") (pintype "input"))
      (node (ref "R166") (pin "1") (pinfunction "1_1") (pintype "input"))
    )
    (net (code "333") (name "Net-(P23-Pad5)") (class "Default")
      (node (ref "P23") (pin "5") (pinfunction "5_5") (pintype "input"))
      (node (ref "R165") (pin "1") (pinfunction "1_1") (pintype "input"))
    )
    (net (code "334") (name "Net-(P23-Pad6)") (class "Default")
      (node (ref "P23") (pin "6") (pinfunction "6_6") (pintype "input"))
      (node (ref "R164") (pin "1") (pinfunction "1_1") (pintype "input"))
    )
    (net (code "335") (name "Net-(P23-Pad7)") (class "Default")
      (node (ref "P23") (pin "7") (pinfunction "7_7") (pintype "input"))
      (node (ref "R163") (pin "1") (pinfunction "1_1") (pintype "input"))
    )
    (net (code "336") (name "Net-(P23-Pad8)") (class "Default")
      (node (ref "P23") (pin "8") (pinfunction "8_8") (pintype "input"))
      (node (ref "R162") (pin "1") (pinfunction "1_1") (pintype "input"))
    )
    (net (code "337") (name "Net-(P24-Pad1)") (class "Default")
      (node (ref "P24") (pin "1") (pinfunction "1_1") (pintype "input"))
      (node (ref "R177") (pin "1") (pinfunction "1_1") (pintype "input"))
    )
    (net (code "338") (name "Net-(P24-Pad2)") (class "Default")
      (node (ref "P24") (pin "2") (pinfunction "2_2") (pintype "input"))
      (node (ref "R176") (pin "1") (pinfunction "1_1") (pintype "input"))
    )
    (net (code "339") (name "Net-(P24-Pad3)") (class "Default")
      (node (ref "P24") (pin "3") (pinfunction "3_3") (pintype "input"))
      (node (ref "R175") (pin "1") (pinfunction "1_1") (pintype "input"))
    )
    (net (code "340") (name "Net-(P24-Pad4)") (class "Default")
      (node (ref "P24") (pin "4") (pinfunction "4_4") (pintype "input"))
      (node (ref "R174") (pin "1") (pinfunction "1_1") (pintype "input"))
    )
    (net (code "341") (name "Net-(P24-Pad5)") (class "Default")
      (node (ref "P24") (pin "5") (pinfunction "5_5") (pintype "input"))
      (node (ref "R173") (pin "1") (pinfunction "1_1") (pintype "input"))
    )
    (net (code "342") (name "Net-(P24-Pad6)") (class "Default")
      (node (ref "P24") (pin "6") (pinfunction "6_6") (pintype "input"))
      (node (ref "R172") (pin "1") (pinfunction "1_1") (pintype "input"))
    )
    (net (code "343") (name "Net-(P24-Pad7)") (class "Default")
      (node (ref "P24") (pin "7") (pinfunction "7_7") (pintype "input"))
      (node (ref "R171") (pin "1") (pinfunction "1_1") (pintype "input"))
    )
    (net (code "344") (name "Net-(P24-Pad8)") (class "Default")
      (node (ref "P24") (pin "8") (pinfunction "8_8") (pintype "input"))
      (node (ref "R170") (pin "1") (pinfunction "1_1") (pintype "input"))
    )
    (net (code "345") (name "Net-(P25-Pad1)") (class "Default")
      (node (ref "P25") (pin "1") (pinfunction "1_1") (pintype "input"))
      (node (ref "R185") (pin "1") (pinfunction "1_1") (pintype "input"))
    )
    (net (code "346") (name "Net-(P25-Pad2)") (class "Default")
      (node (ref "P25") (pin "2") (pinfunction "2_2") (pintype "input"))
      (node (ref "R184") (pin "1") (pinfunction "1_1") (pintype "input"))
    )
    (net (code "347") (name "Net-(P25-Pad3)") (class "Default")
      (node (ref "P25") (pin "3") (pinfunction "3_3") (pintype "input"))
      (node (ref "R183") (pin "1") (pinfunction "1_1") (pintype "input"))
    )
    (net (code "348") (name "Net-(P25-Pad4)") (class "Default")
      (node (ref "P25") (pin "4") (pinfunction "4_4") (pintype "input"))
      (node (ref "R182") (pin "1") (pinfunction "1_1") (pintype "input"))
    )
    (net (code "349") (name "Net-(P25-Pad5)") (class "Default")
      (node (ref "P25") (pin "5") (pinfunction "5_5") (pintype "input"))
      (node (ref "R181") (pin "1") (pinfunction "1_1") (pintype "input"))
    )
    (net (code "350") (name "Net-(P25-Pad6)") (class "Default")
      (node (ref "P25") (pin "6") (pinfunction "6_6") (pintype "input"))
      (node (ref "R180") (pin "1") (pinfunction "1_1") (pintype "input"))
    )
    (net (code "351") (name "Net-(P25-Pad7)") (class "Default")
      (node (ref "P25") (pin "7") (pinfunction "7_7") (pintype "input"))
      (node (ref "R179") (pin "1") (pinfunction "1_1") (pintype "input"))
    )
    (net (code "352") (name "Net-(P25-Pad8)") (class "Default")
      (node (ref "P25") (pin "8") (pinfunction "8_8") (pintype "input"))
      (node (ref "R178") (pin "1") (pinfunction "1_1") (pintype "input"))
    )
    (net (code "353") (name "Net-(P26-Pad1)") (class "Default")
      (node (ref "P26") (pin "1") (pinfunction "1_1") (pintype "input"))
      (node (ref "R193") (pin "1") (pinfunction "1_1") (pintype "input"))
    )
    (net (code "354") (name "Net-(P26-Pad2)") (class "Default")
      (node (ref "P26") (pin "2") (pinfunction "2_2") (pintype "input"))
      (node (ref "R192") (pin "1") (pinfunction "1_1") (pintype "input"))
    )
    (net (code "355") (name "Net-(P26-Pad3)") (class "Default")
      (node (ref "P26") (pin "3") (pinfunction "3_3") (pintype "input"))
      (node (ref "R191") (pin "1") (pinfunction "1_1") (pintype "input"))
    )
    (net (code "356") (name "Net-(P26-Pad4)") (class "Default")
      (node (ref "P26") (pin "4") (pinfunction "4_4") (pintype "input"))
      (node (ref "R190") (pin "1") (pinfunction "1_1") (pintype "input"))
    )
    (net (code "357") (name "Net-(P26-Pad5)") (class "Default")
      (node (ref "P26") (pin "5") (pinfunction "5_5") (pintype "input"))
      (node (ref "R189") (pin "1") (pinfunction "1_1") (pintype "input"))
    )
    (net (code "358") (name "Net-(P26-Pad6)") (class "Default")
      (node (ref "P26") (pin "6") (pinfunction "6_6") (pintype "input"))
      (node (ref "R188") (pin "1") (pinfunction "1_1") (pintype "input"))
    )
    (net (code "359") (name "Net-(P26-Pad7)") (class "Default")
      (node (ref "P26") (pin "7") (pinfunction "7_7") (pintype "input"))
      (node (ref "R187") (pin "1") (pinfunction "1_1") (pintype "input"))
    )
    (net (code "360") (name "Net-(P26-Pad8)") (class "Default")
      (node (ref "P26") (pin "8") (pinfunction "8_8") (pintype "input"))
      (node (ref "R186") (pin "1") (pinfunction "1_1") (pintype "input"))
    )
    (net (code "361") (name "Net-(ROT1-QA)") (class "Default")
      (node (ref "R1") (pin "2") (pinfunction "2_2") (pintype "input"))
      (node (ref "ROT1") (pin "15") (pinfunction "QA_15") (pintype "unspecified"))
    )
    (net (code "362") (name "Net-(ROT1-QB)") (class "Default")
      (node (ref "R2") (pin "2") (pinfunction "2_2") (pintype "input"))
      (node (ref "ROT1") (pin "1") (pinfunction "QB_1") (pintype "unspecified"))
    )
    (net (code "363") (name "Net-(ROT1-QC)") (class "Default")
      (node (ref "R3") (pin "2") (pinfunction "2_2") (pintype "input"))
      (node (ref "ROT1") (pin "2") (pinfunction "QC_2") (pintype "unspecified"))
    )
    (net (code "364") (name "Net-(ROT1-QD)") (class "Default")
      (node (ref "R4") (pin "2") (pinfunction "2_2") (pintype "input"))
      (node (ref "ROT1") (pin "3") (pinfunction "QD_3") (pintype "unspecified"))
    )
    (net (code "365") (name "Net-(ROT1-QE)") (class "Default")
      (node (ref "R5") (pin "2") (pinfunction "2_2") (pintype "input"))
      (node (ref "ROT1") (pin "4") (pinfunction "QE_4") (pintype "unspecified"))
    )
    (net (code "366") (name "Net-(ROT1-QF)") (class "Default")
      (node (ref "R6") (pin "2") (pinfunction "2_2") (pintype "input"))
      (node (ref "ROT1") (pin "5") (pinfunction "QF_5") (pintype "unspecified"))
    )
    (net (code "367") (name "Net-(ROT1-QG)") (class "Default")
      (node (ref "R7") (pin "2") (pinfunction "2_2") (pintype "input"))
      (node (ref "ROT1") (pin "6") (pinfunction "QG_6") (pintype "unspecified"))
    )
    (net (code "368") (name "Net-(ROT1-QH)") (class "Default")
      (node (ref "R8") (pin "2") (pinfunction "2_2") (pintype "input"))
      (node (ref "ROT1") (pin "7") (pinfunction "QH_7") (pintype "unspecified"))
    )
    (net (code "369") (name "Net-(ROT1-QH{slash}2)") (class "Default")
      (node (ref "ROT1") (pin "9") (pinfunction "QH/2_9") (pintype "unspecified"))
      (node (ref "ROT2") (pin "14") (pinfunction "SER_14") (pintype "unspecified"))
    )
    (net (code "370") (name "Net-(ROT2-QA)") (class "Default")
      (node (ref "R9") (pin "2") (pinfunction "2_2") (pintype "input"))
      (node (ref "ROT2") (pin "15") (pinfunction "QA_15") (pintype "unspecified"))
    )
    (net (code "371") (name "Net-(ROT2-QB)") (class "Default")
      (node (ref "R10") (pin "2") (pinfunction "2_2") (pintype "input"))
      (node (ref "ROT2") (pin "1") (pinfunction "QB_1") (pintype "unspecified"))
    )
    (net (code "372") (name "Net-(ROT2-QC)") (class "Default")
      (node (ref "R11") (pin "2") (pinfunction "2_2") (pintype "input"))
      (node (ref "ROT2") (pin "2") (pinfunction "QC_2") (pintype "unspecified"))
    )
    (net (code "373") (name "Net-(ROT2-QD)") (class "Default")
      (node (ref "R12") (pin "2") (pinfunction "2_2") (pintype "input"))
      (node (ref "ROT2") (pin "3") (pinfunction "QD_3") (pintype "unspecified"))
    )
    (net (code "374") (name "Net-(ROT2-QE)") (class "Default")
      (node (ref "R13") (pin "2") (pinfunction "2_2") (pintype "input"))
      (node (ref "ROT2") (pin "4") (pinfunction "QE_4") (pintype "unspecified"))
    )
    (net (code "375") (name "Net-(ROT2-QF)") (class "Default")
      (node (ref "R14") (pin "2") (pinfunction "2_2") (pintype "input"))
      (node (ref "ROT2") (pin "5") (pinfunction "QF_5") (pintype "unspecified"))
    )
    (net (code "376") (name "Net-(ROT2-QG)") (class "Default")
      (node (ref "R15") (pin "2") (pinfunction "2_2") (pintype "input"))
      (node (ref "ROT2") (pin "6") (pinfunction "QG_6") (pintype "unspecified"))
    )
    (net (code "377") (name "Net-(ROT2-QH)") (class "Default")
      (node (ref "R16") (pin "2") (pinfunction "2_2") (pintype "input"))
      (node (ref "ROT2") (pin "7") (pinfunction "QH_7") (pintype "unspecified"))
    )
    (net (code "378") (name "Net-(ROT2-QH{slash}2)") (class "Default")
      (node (ref "ROT2") (pin "9") (pinfunction "QH/2_9") (pintype "unspecified"))
      (node (ref "ROT3") (pin "14") (pinfunction "SER_14") (pintype "unspecified"))
    )
    (net (code "379") (name "Net-(ROT3-QA)") (class "Default")
      (node (ref "R17") (pin "2") (pinfunction "2_2") (pintype "input"))
      (node (ref "ROT3") (pin "15") (pinfunction "QA_15") (pintype "unspecified"))
    )
    (net (code "380") (name "Net-(ROT3-QB)") (class "Default")
      (node (ref "R18") (pin "2") (pinfunction "2_2") (pintype "input"))
      (node (ref "ROT3") (pin "1") (pinfunction "QB_1") (pintype "unspecified"))
    )
    (net (code "381") (name "Net-(ROT3-QC)") (class "Default")
      (node (ref "R19") (pin "2") (pinfunction "2_2") (pintype "input"))
      (node (ref "ROT3") (pin "2") (pinfunction "QC_2") (pintype "unspecified"))
    )
    (net (code "382") (name "Net-(ROT3-QD)") (class "Default")
      (node (ref "R21") (pin "2") (pinfunction "2_2") (pintype "input"))
      (node (ref "ROT3") (pin "3") (pinfunction "QD_3") (pintype "unspecified"))
    )
    (net (code "383") (name "Net-(ROT3-QE)") (class "Default")
      (node (ref "R22") (pin "2") (pinfunction "2_2") (pintype "input"))
      (node (ref "ROT3") (pin "4") (pinfunction "QE_4") (pintype "unspecified"))
    )
    (net (code "384") (name "Net-(ROT3-QF)") (class "Default")
      (node (ref "R23") (pin "2") (pinfunction "2_2") (pintype "input"))
      (node (ref "ROT3") (pin "5") (pinfunction "QF_5") (pintype "unspecified"))
    )
    (net (code "385") (name "Net-(ROT3-QG)") (class "Default")
      (node (ref "R24") (pin "2") (pinfunction "2_2") (pintype "input"))
      (node (ref "ROT3") (pin "6") (pinfunction "QG_6") (pintype "unspecified"))
    )
    (net (code "386") (name "Net-(ROT3-QH)") (class "Default")
      (node (ref "R25") (pin "2") (pinfunction "2_2") (pintype "input"))
      (node (ref "ROT3") (pin "7") (pinfunction "QH_7") (pintype "unspecified"))
    )
    (net (code "387") (name "Net-(ROT3-QH{slash}2)") (class "Default")
      (node (ref "ROT3") (pin "9") (pinfunction "QH/2_9") (pintype "unspecified"))
      (node (ref "ROT4") (pin "14") (pinfunction "SER_14") (pintype "unspecified"))
    )
    (net (code "388") (name "Net-(ROT4-QA)") (class "Default")
      (node (ref "R26") (pin "2") (pinfunction "2_2") (pintype "input"))
      (node (ref "ROT4") (pin "15") (pinfunction "QA_15") (pintype "unspecified"))
    )
    (net (code "389") (name "Net-(ROT4-QB)") (class "Default")
      (node (ref "R27") (pin "2") (pinfunction "2_2") (pintype "input"))
      (node (ref "ROT4") (pin "1") (pinfunction "QB_1") (pintype "unspecified"))
    )
    (net (code "390") (name "Net-(ROT4-QC)") (class "Default")
      (node (ref "R28") (pin "2") (pinfunction "2_2") (pintype "input"))
      (node (ref "ROT4") (pin "2") (pinfunction "QC_2") (pintype "unspecified"))
    )
    (net (code "391") (name "Net-(ROT4-QD)") (class "Default")
      (node (ref "R29") (pin "2") (pinfunction "2_2") (pintype "input"))
      (node (ref "ROT4") (pin "3") (pinfunction "QD_3") (pintype "unspecified"))
    )
    (net (code "392") (name "Net-(ROT4-QE)") (class "Default")
      (node (ref "R30") (pin "2") (pinfunction "2_2") (pintype "input"))
      (node (ref "ROT4") (pin "4") (pinfunction "QE_4") (pintype "unspecified"))
    )
    (net (code "393") (name "Net-(ROT4-QF)") (class "Default")
      (node (ref "R31") (pin "2") (pinfunction "2_2") (pintype "input"))
      (node (ref "ROT4") (pin "5") (pinfunction "QF_5") (pintype "unspecified"))
    )
    (net (code "394") (name "Net-(ROT4-QG)") (class "Default")
      (node (ref "R32") (pin "2") (pinfunction "2_2") (pintype "input"))
      (node (ref "ROT4") (pin "6") (pinfunction "QG_6") (pintype "unspecified"))
    )
    (net (code "395") (name "Net-(ROT4-QH)") (class "Default")
      (node (ref "R33") (pin "2") (pinfunction "2_2") (pintype "input"))
      (node (ref "ROT4") (pin "7") (pinfunction "QH_7") (pintype "unspecified"))
    )
    (net (code "396") (name "Net-(ROT4-QH{slash}2)") (class "Default")
      (node (ref "ROT4") (pin "9") (pinfunction "QH/2_9") (pintype "unspecified"))
      (node (ref "ROT5") (pin "14") (pinfunction "SER_14") (pintype "unspecified"))
    )
    (net (code "397") (name "Net-(ROT5-GND)") (class "Default")
      (node (ref "ROT5") (pin "13") (pinfunction "OE_13") (pintype "unspecified"))
      (node (ref "ROT5") (pin "8") (pinfunction "GND_8") (pintype "unspecified"))
      (node (ref "ROT6") (pin "13") (pinfunction "OE_13") (pintype "unspecified"))
      (node (ref "ROT6") (pin "8") (pinfunction "GND_8") (pintype "unspecified"))
      (node (ref "ROT7") (pin "13") (pinfunction "OE_13") (pintype "unspecified"))
      (node (ref "ROT7") (pin "8") (pinfunction "GND_8") (pintype "unspecified"))
      (node (ref "ROT8") (pin "13") (pinfunction "OE_13") (pintype "unspecified"))
      (node (ref "ROT8") (pin "8") (pinfunction "GND_8") (pintype "unspecified"))
    )
    (net (code "398") (name "Net-(ROT5-QA)") (class "Default")
      (node (ref "R42") (pin "2") (pinfunction "2_2") (pintype "input"))
      (node (ref "ROT5") (pin "15") (pinfunction "QA_15") (pintype "unspecified"))
    )
    (net (code "399") (name "Net-(ROT5-QB)") (class "Default")
      (node (ref "R43") (pin "2") (pinfunction "2_2") (pintype "input"))
      (node (ref "ROT5") (pin "1") (pinfunction "QB_1") (pintype "unspecified"))
    )
    (net (code "400") (name "Net-(ROT5-QC)") (class "Default")
      (node (ref "R44") (pin "2") (pinfunction "2_2") (pintype "input"))
      (node (ref "ROT5") (pin "2") (pinfunction "QC_2") (pintype "unspecified"))
    )
    (net (code "401") (name "Net-(ROT5-QD)") (class "Default")
      (node (ref "R45") (pin "2") (pinfunction "2_2") (pintype "input"))
      (node (ref "ROT5") (pin "3") (pinfunction "QD_3") (pintype "unspecified"))
    )
    (net (code "402") (name "Net-(ROT5-QE)") (class "Default")
      (node (ref "R46") (pin "2") (pinfunction "2_2") (pintype "input"))
      (node (ref "ROT5") (pin "4") (pinfunction "QE_4") (pintype "unspecified"))
    )
    (net (code "403") (name "Net-(ROT5-QF)") (class "Default")
      (node (ref "R47") (pin "2") (pinfunction "2_2") (pintype "input"))
      (node (ref "ROT5") (pin "5") (pinfunction "QF_5") (pintype "unspecified"))
    )
    (net (code "404") (name "Net-(ROT5-QG)") (class "Default")
      (node (ref "R48") (pin "2") (pinfunction "2_2") (pintype "input"))
      (node (ref "ROT5") (pin "6") (pinfunction "QG_6") (pintype "unspecified"))
    )
    (net (code "405") (name "Net-(ROT5-QH)") (class "Default")
      (node (ref "R49") (pin "2") (pinfunction "2_2") (pintype "input"))
      (node (ref "ROT5") (pin "7") (pinfunction "QH_7") (pintype "unspecified"))
    )
    (net (code "406") (name "Net-(ROT5-QH{slash}2)") (class "Default")
      (node (ref "ROT5") (pin "9") (pinfunction "QH/2_9") (pintype "unspecified"))
      (node (ref "ROT6") (pin "14") (pinfunction "SER_14") (pintype "unspecified"))
    )
    (net (code "407") (name "Net-(ROT5-RCLK)") (class "Default")
      (node (ref "ROT5") (pin "12") (pinfunction "RCLK_12") (pintype "unspecified"))
      (node (ref "ROT6") (pin "12") (pinfunction "RCLK_12") (pintype "unspecified"))
      (node (ref "ROT7") (pin "12") (pinfunction "RCLK_12") (pintype "unspecified"))
      (node (ref "ROT8") (pin "12") (pinfunction "RCLK_12") (pintype "unspecified"))
    )
    (net (code "408") (name "Net-(ROT5-SRCLK)") (class "Default")
      (node (ref "ROT5") (pin "11") (pinfunction "SRCLK_11") (pintype "unspecified"))
      (node (ref "ROT6") (pin "11") (pinfunction "SRCLK_11") (pintype "unspecified"))
      (node (ref "ROT7") (pin "11") (pinfunction "SRCLK_11") (pintype "unspecified"))
      (node (ref "ROT8") (pin "11") (pinfunction "SRCLK_11") (pintype "unspecified"))
    )
    (net (code "409") (name "Net-(ROT5-SRCLR)") (class "Default")
      (node (ref "ROT5") (pin "10") (pinfunction "SRCLR_10") (pintype "unspecified"))
      (node (ref "ROT5") (pin "16") (pinfunction "VCC_16") (pintype "unspecified"))
      (node (ref "ROT6") (pin "10") (pinfunction "SRCLR_10") (pintype "unspecified"))
      (node (ref "ROT6") (pin "16") (pinfunction "VCC_16") (pintype "unspecified"))
      (node (ref "ROT7") (pin "10") (pinfunction "SRCLR_10") (pintype "unspecified"))
      (node (ref "ROT7") (pin "16") (pinfunction "VCC_16") (pintype "unspecified"))
      (node (ref "ROT8") (pin "10") (pinfunction "SRCLR_10") (pintype "unspecified"))
      (node (ref "ROT8") (pin "16") (pinfunction "VCC_16") (pintype "unspecified"))
    )
    (net (code "410") (name "Net-(ROT6-QA)") (class "Default")
      (node (ref "R50") (pin "2") (pinfunction "2_2") (pintype "input"))
      (node (ref "ROT6") (pin "15") (pinfunction "QA_15") (pintype "unspecified"))
    )
    (net (code "411") (name "Net-(ROT6-QB)") (class "Default")
      (node (ref "R51") (pin "2") (pinfunction "2_2") (pintype "input"))
      (node (ref "ROT6") (pin "1") (pinfunction "QB_1") (pintype "unspecified"))
    )
    (net (code "412") (name "Net-(ROT6-QC)") (class "Default")
      (node (ref "R52") (pin "2") (pinfunction "2_2") (pintype "input"))
      (node (ref "ROT6") (pin "2") (pinfunction "QC_2") (pintype "unspecified"))
    )
    (net (code "413") (name "Net-(ROT6-QD)") (class "Default")
      (node (ref "R53") (pin "2") (pinfunction "2_2") (pintype "input"))
      (node (ref "ROT6") (pin "3") (pinfunction "QD_3") (pintype "unspecified"))
    )
    (net (code "414") (name "Net-(ROT6-QE)") (class "Default")
      (node (ref "R54") (pin "2") (pinfunction "2_2") (pintype "input"))
      (node (ref "ROT6") (pin "4") (pinfunction "QE_4") (pintype "unspecified"))
    )
    (net (code "415") (name "Net-(ROT6-QF)") (class "Default")
      (node (ref "R55") (pin "2") (pinfunction "2_2") (pintype "input"))
      (node (ref "ROT6") (pin "5") (pinfunction "QF_5") (pintype "unspecified"))
    )
    (net (code "416") (name "Net-(ROT6-QG)") (class "Default")
      (node (ref "R56") (pin "2") (pinfunction "2_2") (pintype "input"))
      (node (ref "ROT6") (pin "6") (pinfunction "QG_6") (pintype "unspecified"))
    )
    (net (code "417") (name "Net-(ROT6-QH)") (class "Default")
      (node (ref "R57") (pin "2") (pinfunction "2_2") (pintype "input"))
      (node (ref "ROT6") (pin "7") (pinfunction "QH_7") (pintype "unspecified"))
    )
    (net (code "418") (name "Net-(ROT6-QH{slash}2)") (class "Default")
      (node (ref "ROT6") (pin "9") (pinfunction "QH/2_9") (pintype "unspecified"))
      (node (ref "ROT7") (pin "14") (pinfunction "SER_14") (pintype "unspecified"))
    )
    (net (code "419") (name "Net-(ROT7-QA)") (class "Default")
      (node (ref "R58") (pin "2") (pinfunction "2_2") (pintype "input"))
      (node (ref "ROT7") (pin "15") (pinfunction "QA_15") (pintype "unspecified"))
    )
    (net (code "420") (name "Net-(ROT7-QB)") (class "Default")
      (node (ref "R59") (pin "2") (pinfunction "2_2") (pintype "input"))
      (node (ref "ROT7") (pin "1") (pinfunction "QB_1") (pintype "unspecified"))
    )
    (net (code "421") (name "Net-(ROT7-QC)") (class "Default")
      (node (ref "R60") (pin "2") (pinfunction "2_2") (pintype "input"))
      (node (ref "ROT7") (pin "2") (pinfunction "QC_2") (pintype "unspecified"))
    )
    (net (code "422") (name "Net-(ROT7-QD)") (class "Default")
      (node (ref "R61") (pin "2") (pinfunction "2_2") (pintype "input"))
      (node (ref "ROT7") (pin "3") (pinfunction "QD_3") (pintype "unspecified"))
    )
    (net (code "423") (name "Net-(ROT7-QE)") (class "Default")
      (node (ref "R62") (pin "2") (pinfunction "2_2") (pintype "input"))
      (node (ref "ROT7") (pin "4") (pinfunction "QE_4") (pintype "unspecified"))
    )
    (net (code "424") (name "Net-(ROT7-QF)") (class "Default")
      (node (ref "R63") (pin "2") (pinfunction "2_2") (pintype "input"))
      (node (ref "ROT7") (pin "5") (pinfunction "QF_5") (pintype "unspecified"))
    )
    (net (code "425") (name "Net-(ROT7-QG)") (class "Default")
      (node (ref "R64") (pin "2") (pinfunction "2_2") (pintype "input"))
      (node (ref "ROT7") (pin "6") (pinfunction "QG_6") (pintype "unspecified"))
    )
    (net (code "426") (name "Net-(ROT7-QH)") (class "Default")
      (node (ref "R65") (pin "2") (pinfunction "2_2") (pintype "input"))
      (node (ref "ROT7") (pin "7") (pinfunction "QH_7") (pintype "unspecified"))
    )
    (net (code "427") (name "Net-(ROT7-QH{slash}2)") (class "Default")
      (node (ref "ROT7") (pin "9") (pinfunction "QH/2_9") (pintype "unspecified"))
      (node (ref "ROT8") (pin "14") (pinfunction "SER_14") (pintype "unspecified"))
    )
    (net (code "428") (name "Net-(ROT8-QA)") (class "Default")
      (node (ref "R66") (pin "2") (pinfunction "2_2") (pintype "input"))
      (node (ref "ROT8") (pin "15") (pinfunction "QA_15") (pintype "unspecified"))
    )
    (net (code "429") (name "Net-(ROT8-QB)") (class "Default")
      (node (ref "R67") (pin "2") (pinfunction "2_2") (pintype "input"))
      (node (ref "ROT8") (pin "1") (pinfunction "QB_1") (pintype "unspecified"))
    )
    (net (code "430") (name "Net-(ROT8-QC)") (class "Default")
      (node (ref "R68") (pin "2") (pinfunction "2_2") (pintype "input"))
      (node (ref "ROT8") (pin "2") (pinfunction "QC_2") (pintype "unspecified"))
    )
    (net (code "431") (name "Net-(ROT8-QD)") (class "Default")
      (node (ref "R69") (pin "2") (pinfunction "2_2") (pintype "input"))
      (node (ref "ROT8") (pin "3") (pinfunction "QD_3") (pintype "unspecified"))
    )
    (net (code "432") (name "Net-(ROT8-QE)") (class "Default")
      (node (ref "R70") (pin "2") (pinfunction "2_2") (pintype "input"))
      (node (ref "ROT8") (pin "4") (pinfunction "QE_4") (pintype "unspecified"))
    )
    (net (code "433") (name "Net-(ROT8-QF)") (class "Default")
      (node (ref "R71") (pin "2") (pinfunction "2_2") (pintype "input"))
      (node (ref "ROT8") (pin "5") (pinfunction "QF_5") (pintype "unspecified"))
    )
    (net (code "434") (name "Net-(ROT8-QG)") (class "Default")
      (node (ref "R72") (pin "2") (pinfunction "2_2") (pintype "input"))
      (node (ref "ROT8") (pin "6") (pinfunction "QG_6") (pintype "unspecified"))
    )
    (net (code "435") (name "Net-(ROT8-QH)") (class "Default")
      (node (ref "R73") (pin "2") (pinfunction "2_2") (pintype "input"))
      (node (ref "ROT8") (pin "7") (pinfunction "QH_7") (pintype "unspecified"))
    )
    (net (code "436") (name "RCLK") (class "Default")
      (node (ref "BLAU1") (pin "12") (pinfunction "RCLK_12") (pintype "unspecified"))
      (node (ref "BLAU2") (pin "12") (pinfunction "RCLK_12") (pintype "unspecified"))
      (node (ref "BLAU3") (pin "12") (pinfunction "RCLK_12") (pintype "unspecified"))
      (node (ref "BLAU4") (pin "12") (pinfunction "RCLK_12") (pintype "unspecified"))
      (node (ref "GRUEN1") (pin "12") (pinfunction "RCLK_12") (pintype "unspecified"))
      (node (ref "GRUEN2") (pin "12") (pinfunction "RCLK_12") (pintype "unspecified"))
      (node (ref "GRUEN3") (pin "12") (pinfunction "RCLK_12") (pintype "unspecified"))
      (node (ref "GRUEN4") (pin "12") (pinfunction "RCLK_12") (pintype "unspecified"))
      (node (ref "P12") (pin "3") (pinfunction "3_3") (pintype "input"))
      (node (ref "ROT1") (pin "12") (pinfunction "RCLK_12") (pintype "unspecified"))
      (node (ref "ROT2") (pin "12") (pinfunction "RCLK_12") (pintype "unspecified"))
      (node (ref "ROT3") (pin "12") (pinfunction "RCLK_12") (pintype "unspecified"))
      (node (ref "ROT4") (pin "12") (pinfunction "RCLK_12") (pintype "unspecified"))
    )
    (net (code "437") (name "SRCLK") (class "Default")
      (node (ref "BLAU1") (pin "11") (pinfunction "SRCLK_11") (pintype "unspecified"))
      (node (ref "BLAU2") (pin "11") (pinfunction "SRCLK_11") (pintype "unspecified"))
      (node (ref "BLAU3") (pin "11") (pinfunction "SRCLK_11") (pintype "unspecified"))
      (node (ref "BLAU4") (pin "11") (pinfunction "SRCLK_11") (pintype "unspecified"))
      (node (ref "GRUEN1") (pin "11") (pinfunction "SRCLK_11") (pintype "unspecified"))
      (node (ref "GRUEN2") (pin "11") (pinfunction "SRCLK_11") (pintype "unspecified"))
      (node (ref "GRUEN3") (pin "11") (pinfunction "SRCLK_11") (pintype "unspecified"))
      (node (ref "GRUEN4") (pin "11") (pinfunction "SRCLK_11") (pintype "unspecified"))
      (node (ref "P12") (pin "2") (pinfunction "2_2") (pintype "input"))
      (node (ref "ROT1") (pin "11") (pinfunction "SRCLK_11") (pintype "unspecified"))
      (node (ref "ROT2") (pin "11") (pinfunction "SRCLK_11") (pintype "unspecified"))
      (node (ref "ROT3") (pin "11") (pinfunction "SRCLK_11") (pintype "unspecified"))
      (node (ref "ROT4") (pin "11") (pinfunction "SRCLK_11") (pintype "unspecified"))
    )
    (net (code "438") (name "Serial Data") (class "Default")
      (node (ref "P12") (pin "1") (pinfunction "1_1") (pintype "input"))
      (node (ref "ROT1") (pin "14") (pinfunction "SER_14") (pintype "unspecified"))
    )
    (net (code "439") (name "Serialout_g") (class "Default")
      (node (ref "BLAU1") (pin "14") (pinfunction "SER_14") (pintype "unspecified"))
      (node (ref "GRUEN8") (pin "9") (pinfunction "QH/2_9") (pintype "unspecified"))
    )
    (net (code "440") (name "unconnected-(BLAU8-QH{slash}2-Pad9)") (class "Default")
      (node (ref "BLAU8") (pin "9") (pinfunction "QH/2_9") (pintype "unspecified+no_connect"))
    )
  )
)
